# COIL-BOOST-10A.net
KiCad netlist of a schematic drawn in Altium Designer
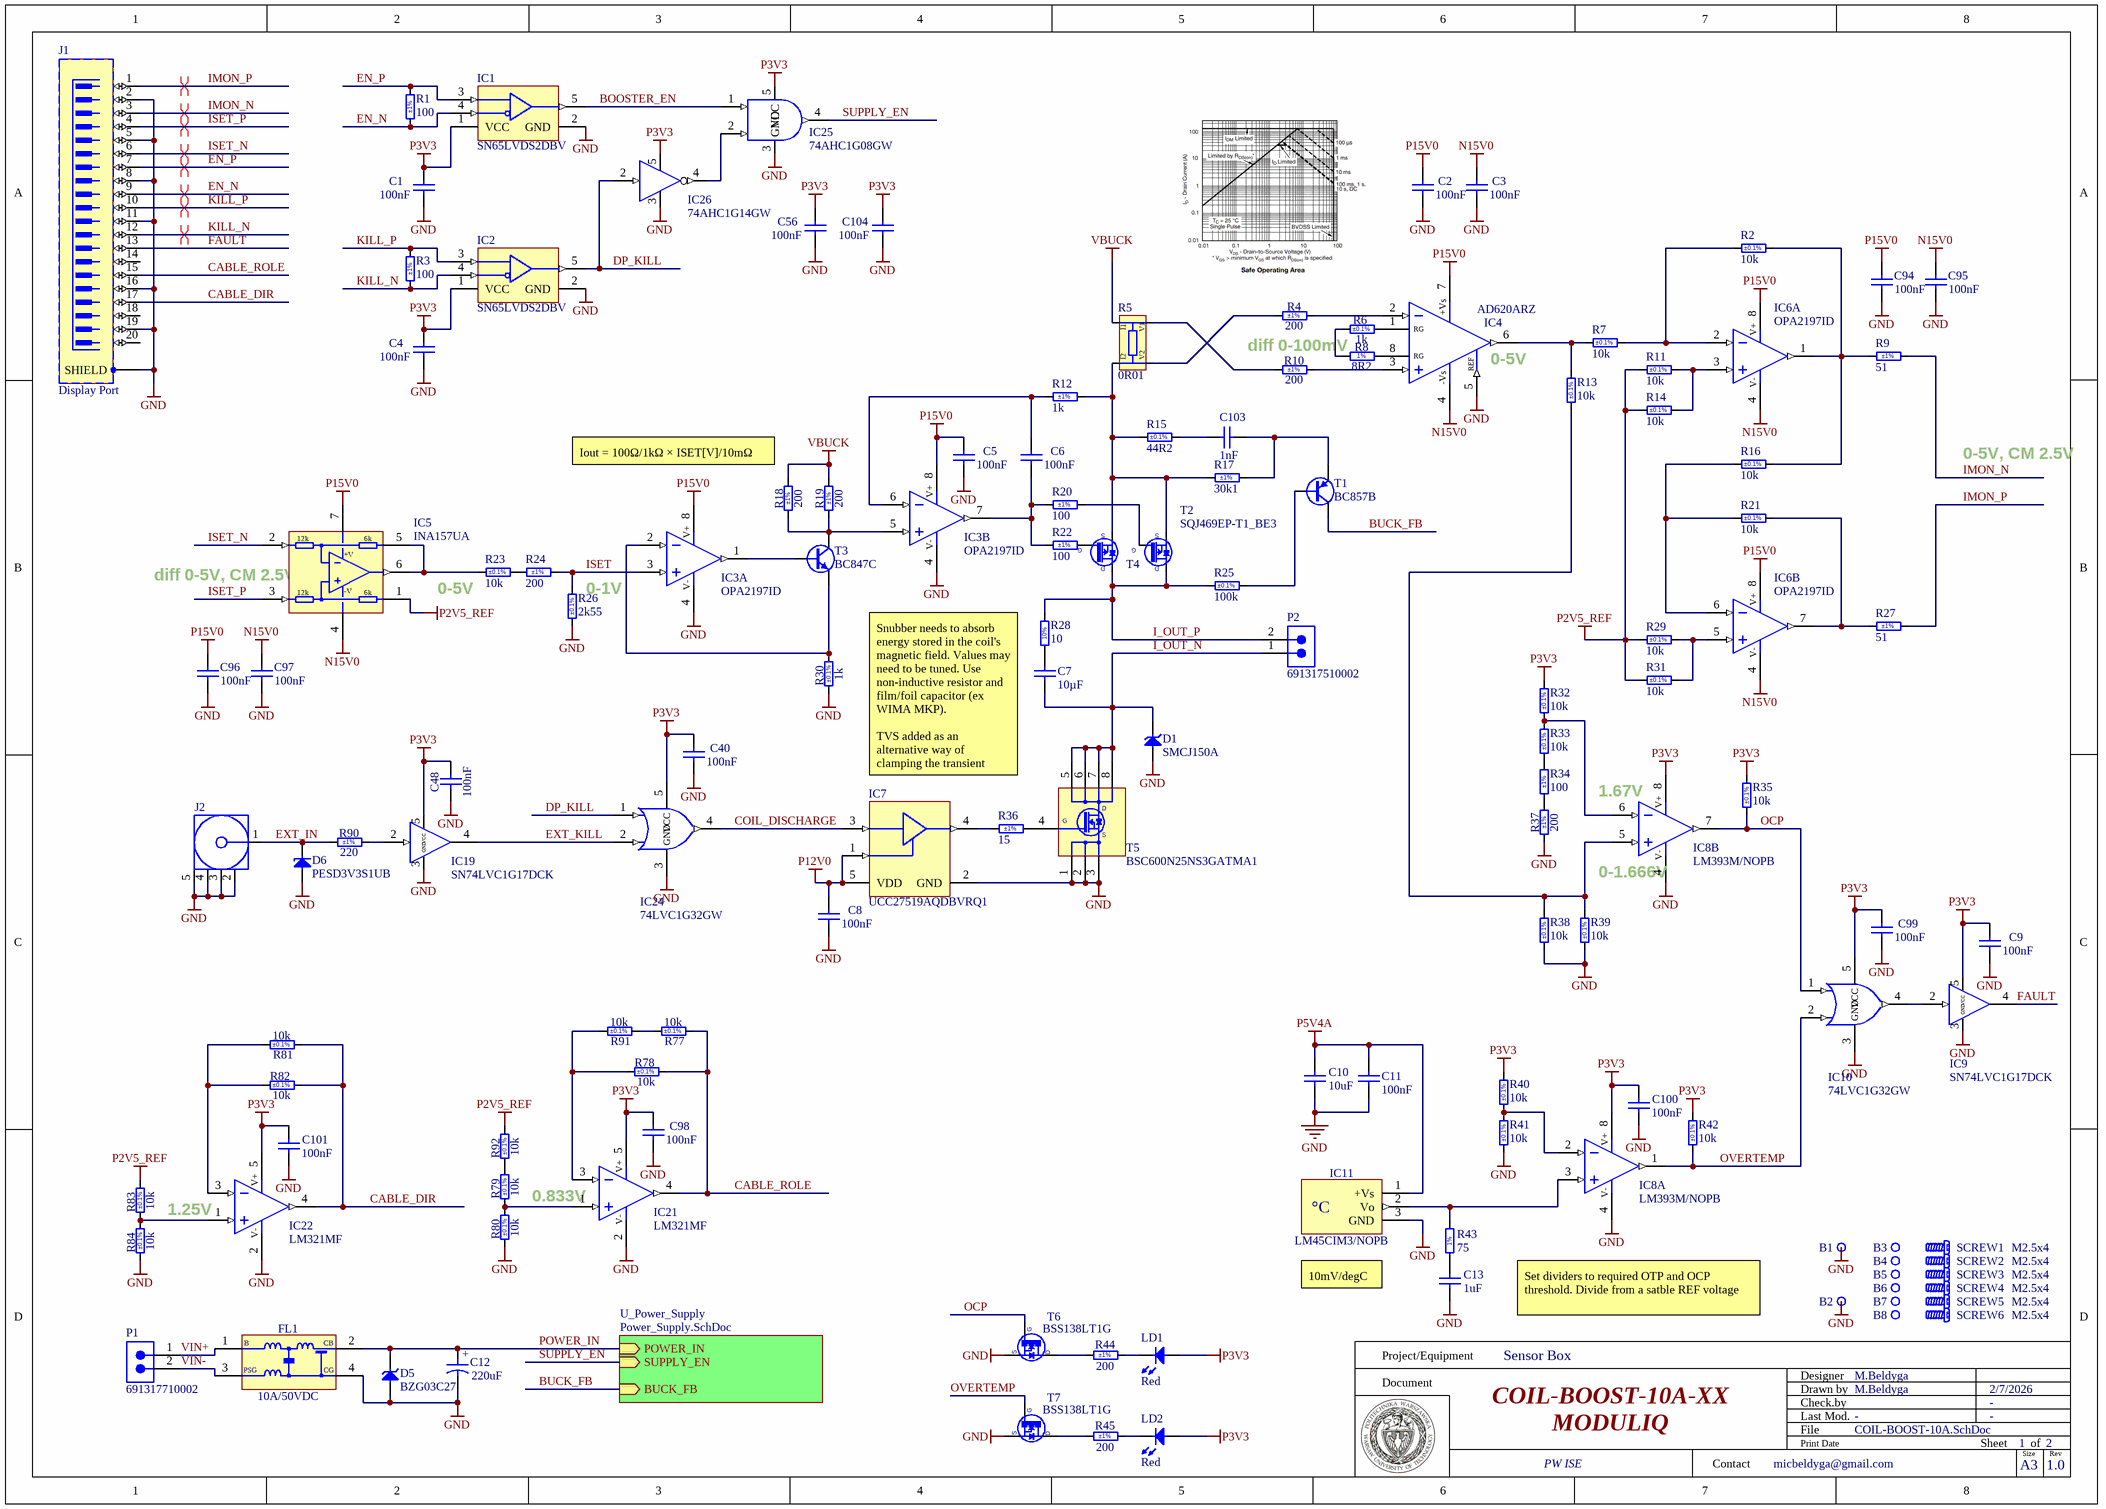
[diagram p0: COIL-BOOST-10A.SchDoc]

(export (version "E")
  (design (tool "Eeschema 10.0.6"))
  (components
    (comp (ref "B1")
      (value "Plated Hole")
      (footprint "MTG270_500")
      (description "Single Terminal Socket")
      (fields (field (name "PART NUMBER") "PLATED_HOLE2.7_PAD5.0") (field (name "AUTHOR") "CERN DEM JMW"))
      (libsource (lib "Eletro-mechanical") (part "Single Terminal Socket"))
    )
    (comp (ref "B2")
      (value "Plated Hole")
      (footprint "MTG270_500")
      (description "Single Terminal Socket")
      (fields (field (name "PART NUMBER") "PLATED_HOLE2.7_PAD5.0") (field (name "AUTHOR") "CERN DEM JMW"))
      (libsource (lib "Eletro-mechanical") (part "Single Terminal Socket"))
    )
    (comp (ref "B3")
      (value "Plated Hole")
      (footprint "MTG270_500")
      (description "Single Terminal Socket")
      (fields (field (name "PART NUMBER") "PLATED_HOLE2.7_PAD5.0") (field (name "AUTHOR") "CERN DEM JMW"))
      (libsource (lib "Eletro-mechanical") (part "Single Terminal Socket"))
    )
    (comp (ref "B4")
      (value "Plated Hole")
      (footprint "MTG270_500")
      (description "Single Terminal Socket")
      (fields (field (name "PART NUMBER") "PLATED_HOLE2.7_PAD5.0") (field (name "AUTHOR") "CERN DEM JMW"))
      (libsource (lib "Eletro-mechanical") (part "Single Terminal Socket"))
    )
    (comp (ref "B5")
      (value "Plated Hole")
      (footprint "MTG270_500")
      (description "Single Terminal Socket")
      (fields (field (name "PART NUMBER") "PLATED_HOLE2.7_PAD5.0") (field (name "AUTHOR") "CERN DEM JMW"))
      (libsource (lib "Eletro-mechanical") (part "Single Terminal Socket"))
    )
    (comp (ref "B6")
      (value "Plated Hole")
      (footprint "MTG270_500")
      (description "Single Terminal Socket")
      (fields (field (name "PART NUMBER") "PLATED_HOLE2.7_PAD5.0") (field (name "AUTHOR") "CERN DEM JMW"))
      (libsource (lib "Eletro-mechanical") (part "Single Terminal Socket"))
    )
    (comp (ref "B7")
      (value "Plated Hole")
      (footprint "MTG270_500")
      (description "Single Terminal Socket")
      (fields (field (name "PART NUMBER") "PLATED_HOLE2.7_PAD5.0") (field (name "AUTHOR") "CERN DEM JMW"))
      (libsource (lib "Eletro-mechanical") (part "Single Terminal Socket"))
    )
    (comp (ref "B8")
      (value "Plated Hole")
      (footprint "MTG270_500")
      (description "Single Terminal Socket")
      (fields (field (name "PART NUMBER") "PLATED_HOLE2.7_PAD5.0") (field (name "AUTHOR") "CERN DEM JMW"))
      (libsource (lib "Eletro-mechanical") (part "Single Terminal Socket"))
    )
    (comp (ref "C1")
      (value "100nF")
      (footprint "CAPC1005X55N")
      (description "Non-polarised capacitor")
      (fields
        (field (name "PART NUMBER") "CC0402_100NF_16V_10%_X5R")
        (field (name "VOLTAGE") "16V")
        (field (name "AUTHOR") "CERN DEM JLC")
      )
      (libsource (lib "Capacitors") (part "Capacitor - non polarized"))
    )
    (comp (ref "C2")
      (value "100nF")
      (footprint "CAPC1005X55N")
      (description "Non-polarised capacitor")
      (fields
        (field (name "PART NUMBER") "CC0402_100NF_16V_10%_X5R")
        (field (name "VOLTAGE") "16V")
        (field (name "AUTHOR") "CERN DEM JLC")
      )
      (libsource (lib "Capacitors") (part "Capacitor - non polarized"))
    )
    (comp (ref "C3")
      (value "100nF")
      (footprint "CAPC1005X55N")
      (description "Non-polarised capacitor")
      (fields
        (field (name "PART NUMBER") "CC0402_100NF_16V_10%_X5R")
        (field (name "VOLTAGE") "16V")
        (field (name "AUTHOR") "CERN DEM JLC")
      )
      (libsource (lib "Capacitors") (part "Capacitor - non polarized"))
    )
    (comp (ref "C4")
      (value "100nF")
      (footprint "CAPC1005X55N")
      (description "Non-polarised capacitor")
      (fields
        (field (name "PART NUMBER") "CC0402_100NF_16V_10%_X5R")
        (field (name "VOLTAGE") "16V")
        (field (name "AUTHOR") "CERN DEM JLC")
      )
      (libsource (lib "Capacitors") (part "Capacitor - non polarized"))
    )
    (comp (ref "C5")
      (value "100nF")
      (footprint "CAPC1005X55N")
      (description "Non-polarised capacitor")
      (fields
        (field (name "PART NUMBER") "CC0402_100NF_16V_10%_X5R")
        (field (name "VOLTAGE") "16V")
        (field (name "AUTHOR") "CERN DEM JLC")
      )
      (libsource (lib "Capacitors") (part "Capacitor - non polarized"))
    )
    (comp (ref "C6")
      (value "100nF")
      (footprint "CAPC1005X55N")
      (description "Non-polarised capacitor")
      (fields
        (field (name "PART NUMBER") "CC0402_100NF_16V_10%_X5R")
        (field (name "VOLTAGE") "16V")
        (field (name "AUTHOR") "CERN DEM JLC")
      )
      (libsource (lib "Capacitors") (part "Capacitor - non polarized"))
    )
    (comp (ref "C7")
      (value "10µF")
      (footprint "Kemet R71 32x28x14")
      (description "Film Capacitor, Polypropylene, 450V, 10% +Tol, 10% -Tol, 10uF, Through Hole Mount")
      (fields
        (field (name "MANUFACTURER") "KEMET")
        (field (name "MANUFACTURER PART NUMBER") "R71XR510050H0K")
      )
      (libsource (lib "mb") (part "R71XR510050H0K"))
    )
    (comp (ref "C8")
      (value "100nF")
      (footprint "CAPC1005X55N")
      (description "Non-polarised capacitor")
      (fields
        (field (name "PART NUMBER") "CC0402_100NF_16V_10%_X5R")
        (field (name "VOLTAGE") "16V")
        (field (name "AUTHOR") "CERN DEM JLC")
      )
      (libsource (lib "Capacitors") (part "Capacitor - non polarized"))
    )
    (comp (ref "C9")
      (value "100nF")
      (footprint "CAPC1005X55N")
      (description "Non-polarised capacitor")
      (fields
        (field (name "PART NUMBER") "CC0402_100NF_16V_10%_X5R")
        (field (name "VOLTAGE") "16V")
        (field (name "AUTHOR") "CERN DEM JLC")
      )
      (libsource (lib "Capacitors") (part "Capacitor - non polarized"))
    )
    (comp (ref "C10")
      (value "10uF")
      (footprint "CAPC1608X80N")
      (description "Non-polarised capacitor")
      (fields
        (field (name "PART NUMBER") "CC0603_10UF_10V_10%_X5R")
        (field (name "VOLTAGE") "10V")
        (field (name "AUTHOR") "CERN DEM JLC")
      )
      (libsource (lib "Capacitors") (part "Capacitor - non polarized"))
    )
    (comp (ref "C11")
      (value "100nF")
      (footprint "CAPC1005X55N")
      (description "Non-polarised capacitor")
      (fields
        (field (name "PART NUMBER") "CC0402_100NF_50V_10%_X7R")
        (field (name "VOLTAGE") "50V")
        (field (name "AUTHOR") "CERN DEM MR")
      )
      (libsource (lib "Capacitors") (part "Capacitor - non polarized"))
    )
    (comp (ref "C12")
      (value "220uF")
      (footprint "CAPAE830X620N")
      (description "Polarised capacitor")
      (fields
        (field (name "PART NUMBER") "CAE830-620_220UF_16V_20%")
        (field (name "VOLTAGE") "16V")
        (field (name "AUTHOR") "CERN DEM JLC")
      )
      (libsource (lib "Capacitors") (part "Capacitor - polarized"))
    )
    (comp (ref "C13")
      (value "1uF")
      (footprint "CAPC1005X55N")
      (description "Non-polarised capacitor")
      (fields
        (field (name "PART NUMBER") "CC0402_1UF_16V_10%_X5R")
        (field (name "VOLTAGE") "16V")
        (field (name "AUTHOR") "CERN DEM JLC")
      )
      (libsource (lib "Capacitors") (part "Capacitor - non polarized"))
    )
    (comp (ref "C40")
      (value "100nF")
      (footprint "CAPC1005X55N")
      (description "Non-polarised capacitor")
      (fields
        (field (name "PART NUMBER") "CC0402_100NF_16V_10%_X5R")
        (field (name "VOLTAGE") "16V")
        (field (name "AUTHOR") "CERN DEM JLC")
      )
      (libsource (lib "Capacitors") (part "Capacitor - non polarized"))
    )
    (comp (ref "C48")
      (value "100nF")
      (footprint "CAPC1005X55N")
      (description "Non-polarised capacitor")
      (fields
        (field (name "PART NUMBER") "CC0402_100NF_16V_10%_X7R")
        (field (name "VOLTAGE") "16V")
        (field (name "AUTHOR") "CERN DEM JLC")
      )
      (libsource (lib "Capacitors") (part "Capacitor - non polarized"))
    )
    (comp (ref "C56")
      (value "100nF")
      (footprint "CAPC1005X55N")
      (description "Non-polarised capacitor")
      (fields
        (field (name "PART NUMBER") "CC0402_100NF_16V_10%_X5R")
        (field (name "VOLTAGE") "16V")
        (field (name "AUTHOR") "CERN DEM JLC")
      )
      (libsource (lib "Capacitors") (part "Capacitor - non polarized"))
    )
    (comp (ref "C94")
      (value "100nF")
      (footprint "CAPC1005X55N")
      (description "Non-polarised capacitor")
      (fields
        (field (name "PART NUMBER") "CC0402_100NF_16V_10%_X5R")
        (field (name "VOLTAGE") "16V")
        (field (name "AUTHOR") "CERN DEM JLC")
      )
      (libsource (lib "Capacitors") (part "Capacitor - non polarized"))
    )
    (comp (ref "C95")
      (value "100nF")
      (footprint "CAPC1005X55N")
      (description "Non-polarised capacitor")
      (fields
        (field (name "PART NUMBER") "CC0402_100NF_16V_10%_X5R")
        (field (name "VOLTAGE") "16V")
        (field (name "AUTHOR") "CERN DEM JLC")
      )
      (libsource (lib "Capacitors") (part "Capacitor - non polarized"))
    )
    (comp (ref "C96")
      (value "100nF")
      (footprint "CAPC1005X55N")
      (description "Non-polarised capacitor")
      (fields
        (field (name "PART NUMBER") "CC0402_100NF_16V_10%_X5R")
        (field (name "VOLTAGE") "16V")
        (field (name "AUTHOR") "CERN DEM JLC")
      )
      (libsource (lib "Capacitors") (part "Capacitor - non polarized"))
    )
    (comp (ref "C97")
      (value "100nF")
      (footprint "CAPC1005X55N")
      (description "Non-polarised capacitor")
      (fields
        (field (name "PART NUMBER") "CC0402_100NF_16V_10%_X5R")
        (field (name "VOLTAGE") "16V")
        (field (name "AUTHOR") "CERN DEM JLC")
      )
      (libsource (lib "Capacitors") (part "Capacitor - non polarized"))
    )
    (comp (ref "C98")
      (value "100nF")
      (footprint "CAPC1005X55N")
      (description "Non-polarised capacitor")
      (fields
        (field (name "PART NUMBER") "CC0402_100NF_16V_10%_X5R")
        (field (name "VOLTAGE") "16V")
        (field (name "AUTHOR") "CERN DEM JLC")
      )
      (libsource (lib "Capacitors") (part "Capacitor - non polarized"))
    )
    (comp (ref "C99")
      (value "100nF")
      (footprint "CAPC1005X55N")
      (description "Non-polarised capacitor")
      (fields
        (field (name "PART NUMBER") "CC0402_100NF_16V_10%_X5R")
        (field (name "VOLTAGE") "16V")
        (field (name "AUTHOR") "CERN DEM JLC")
      )
      (libsource (lib "Capacitors") (part "Capacitor - non polarized"))
    )
    (comp (ref "C100")
      (value "100nF")
      (footprint "CAPC1005X55N")
      (description "Non-polarised capacitor")
      (fields
        (field (name "PART NUMBER") "CC0402_100NF_16V_10%_X5R")
        (field (name "VOLTAGE") "16V")
        (field (name "AUTHOR") "CERN DEM JLC")
      )
      (libsource (lib "Capacitors") (part "Capacitor - non polarized"))
    )
    (comp (ref "C101")
      (value "100nF")
      (footprint "CAPC1005X55N")
      (description "Non-polarised capacitor")
      (fields
        (field (name "PART NUMBER") "CC0402_100NF_16V_10%_X5R")
        (field (name "VOLTAGE") "16V")
        (field (name "AUTHOR") "CERN DEM JLC")
      )
      (libsource (lib "Capacitors") (part "Capacitor - non polarized"))
    )
    (comp (ref "C103")
      (value "1nF")
      (footprint "CAPC1005X55N")
      (description "Non-polarised capacitor")
      (fields
        (field (name "PART NUMBER") "CC0402_1NF_50V_5%_C0G")
        (field (name "VOLTAGE") "50V")
        (field (name "AUTHOR") "CERN DEM BC")
      )
      (libsource (lib "Capacitors") (part "Capacitor - non polarized"))
    )
    (comp (ref "C104")
      (value "100nF")
      (footprint "CAPC1005X55N")
      (description "Non-polarised capacitor")
      (fields
        (field (name "PART NUMBER") "CC0402_100NF_16V_10%_X5R")
        (field (name "VOLTAGE") "16V")
        (field (name "AUTHOR") "CERN DEM JLC")
      )
      (libsource (lib "Capacitors") (part "Capacitor - non polarized"))
    )
    (comp (ref "D1")
      (value "SMCJ150A")
      (footprint "DIOM7959X262N")
      (description "Transient Voltage Suppressor Diode (Uni-Directional)")
      (fields
        (field (name "VOLTAGE") "150V")
        (field (name "POWER") "1500W")
        (field (name "AUTHOR") "CERN DEM BC")
      )
      (libsource (lib "ICs And Semiconductors") (part "Diode TVS Uni-Directional"))
    )
    (comp (ref "D5")
      (value "BZG03C27")
      (footprint "DIOM5326X230N")
      (description "Zener Diode")
      (fields
        (field (name "VOLTAGE") "27V")
        (field (name "POWER") "1.25W")
        (field (name "AUTHOR") "CERN DEM JLC")
      )
      (libsource (lib "ICs And Semiconductors") (part "Diode Zener"))
    )
    (comp (ref "D6")
      (value "PESD3V3S1UB")
      (footprint "SODFL1608X65N")
      (description "ESD protection diode")
      (fields
        (field (name "VOLTAGE") "3V3")
        (field (name "POWER") "330W")
        (field (name "AUTHOR") "CERN DEM JLC")
      )
      (libsource (lib "ICs And Semiconductors") (part "Diode ESD"))
    )
    (comp (ref "FL1")
      (value "10A/50VDC")
      (footprint "FIL_MURATA_BNX02")
      (description "Block Type EMIFIL (LC Combined)")
      (fields
        (field (name "PART NUMBER") "FIL_MURATA_BNX022-01L")
        (field (name "MANUFACTURER1 PART NUMBER") "BNX022-01L")
        (field (name "AUTHOR") "CERN DEM JLC")
      )
      (libsource (lib "Inductors & Transformers") (part "FIL_MURATA_BNX02"))
    )
    (comp (ref "IC1")
      (value "SN65LVDS2DBV")
      (footprint "SOT95P280X145-5N")
      (description "High-Speed Differential Line Receiver")
      (fields
        (field (name "PART NUMBER") "SN65LVDS2DBVR")
        (field (name "MANUFACTURER") "TEXAS INSTRUMENTS")
        (field (name "AUTHOR") "CERN DEM JLC")
      )
      (libsource (lib "ICs And Semiconductors") (part "SN65LVDS2DBV"))
    )
    (comp (ref "IC2")
      (value "SN65LVDS2DBV")
      (footprint "SOT95P280X145-5N")
      (description "High-Speed Differential Line Receiver")
      (fields
        (field (name "PART NUMBER") "SN65LVDS2DBVR")
        (field (name "MANUFACTURER") "TEXAS INSTRUMENTS")
        (field (name "AUTHOR") "CERN DEM JLC")
      )
      (libsource (lib "ICs And Semiconductors") (part "SN65LVDS2DBV"))
    )
    (comp (ref "IC3")
      (value "OPA2197ID")
      (footprint "SOIC127P600X175-8N")
      (description "Dual Operational Amplifier")
      (fields (field (name "MANUFACTURER") "TEXAS INSTRUMENTS") (field (name "AUTHOR") "CERN DEM MR"))
      (libsource (lib "ICs And Semiconductors") (part "Operational Amplifier x2 Type1"))
    )
    (comp (ref "IC4")
      (value "AD620ARZ")
      (footprint "SOIC127P600X175-8N")
      (description "Low Cost Low Power Instrumentation Amplifier")
      (fields
        (field (name "MANUFACTURER1 PART NUMBER") "AD620ARZ-REEL7")
        (field (name "AUTHOR") "CERN DEM JLC")
      )
      (libsource (lib "ICs And Semiconductors") (part "AD620"))
    )
    (comp (ref "IC5")
      (value "INA157UA")
      (footprint "SOIC127P600X175-8N")
      (description "IC OPAMP DIFF 1 CIRCUIT 8SOIC Differential Amplifier 1 Circuit 8-SOIC")
      (fields (field (name "MANUFACTURER") "Texas Instruments"))
      (libsource (lib "mb") (part "INA157UA"))
    )
    (comp (ref "IC6")
      (value "OPA2197ID")
      (footprint "SOIC127P600X175-8N")
      (description "Dual Operational Amplifier")
      (fields (field (name "MANUFACTURER") "TEXAS INSTRUMENTS") (field (name "AUTHOR") "CERN DEM MR"))
      (libsource (lib "ICs And Semiconductors") (part "Operational Amplifier x2 Type1"))
    )
    (comp (ref "IC7")
      (value "UCC27519AQDBVRQ1")
      (footprint "SOT95P280X145-5N")
      (description "Single-Channel High-Speed Low-Side Gate Driver With Negative Input  Voltage Capability")
      (fields
        (field (name "MANUFACTURER") "TEXAS INSTRUMENTS")
        (field (name "MANUFACTURER PART NUMBER") "UCC27519AQDBV")
        (field (name "AUTHOR") "CERN DEM JLC")
      )
      (libsource (lib "ICs And Semiconductors") (part "UCC2751xA-Q1"))
    )
    (comp (ref "IC8")
      (value "LM393M/NOPB")
      (footprint "SOIC127P600X175-8N")
      (description "Dual Operational Amplifier")
      (fields
        (field (name "MANUFACTURER") "NATIONAL SEMICONDUCTOR")
        (field (name "MANUFACTURER PART NUMBER") "LM393M")
        (field (name "AUTHOR") "CERN DEM JLC")
      )
      (libsource (lib "ICs And Semiconductors") (part "Operational Amplifier x2 Type1"))
    )
    (comp (ref "IC9")
      (value "SN74LVC1G17DCK")
      (footprint "SOT65P210X110-5N")
      (description "Single Schmitt-Trigger Buffer")
      (fields (field (name "MANUFACTURER") "TEXAS INSTRUMENTS") (field (name "AUTHOR") "CERN DEM HF"))
      (libsource (lib "mb") (part "SN74LVC1G17DCK"))
    )
    (comp (ref "IC10")
      (value "74LVC1G32GW")
      (footprint "SOT65P212X110-5N")
      (description "Single 2-Input Positive-OR Gate")
      (fields (field (name "MANUFACTURER") "NXP SEMICONDUCTORS") (field (name "AUTHOR") "CERN DEM JLC"))
      (libsource (lib "ICs And Semiconductors") (part "741G32"))
    )
    (comp (ref "IC11")
      (value "LM45CIM3/NOPB")
      (footprint "SOT95P251X112-3N")
      (description "-20° to +100°C ±3°C Precision Centigrade Temperature Sensors")
      (fields (field (name "MANUFACTURER") "TEXAS INSTRUMENTS") (field (name "AUTHOR") "CERN DEM JLC"))
      (libsource (lib "ICs And Semiconductors") (part "LM45"))
    )
    (comp (ref "IC19")
      (value "SN74LVC1G17DCK")
      (footprint "SOT65P210X110-5N")
      (description "Single Schmitt-Trigger Buffer")
      (fields (field (name "MANUFACTURER") "TEXAS INSTRUMENTS") (field (name "AUTHOR") "CERN DEM HF"))
      (libsource (lib "mb") (part "SN74LVC1G17DCK"))
    )
    (comp (ref "IC21")
      (value "LM321MF")
      (footprint "SOT95P280X145-5N")
      (description "Low Power Single Operational Amplifier")
      (fields
        (field (name "PART NUMBER") "LM321MF/NOPB")
        (field (name "MANUFACTURER") "TEXAS INSTRUMENTS")
        (field (name "AUTHOR") "CERN DEM BC")
      )
      (libsource (lib "ICs And Semiconductors") (part "LM321"))
    )
    (comp (ref "IC22")
      (value "LM321MF")
      (footprint "SOT95P280X145-5N")
      (description "Low Power Single Operational Amplifier")
      (fields
        (field (name "PART NUMBER") "LM321MF/NOPB")
        (field (name "MANUFACTURER") "TEXAS INSTRUMENTS")
        (field (name "AUTHOR") "CERN DEM BC")
      )
      (libsource (lib "ICs And Semiconductors") (part "LM321"))
    )
    (comp (ref "IC24")
      (value "74LVC1G32GW")
      (footprint "SOT65P212X110-5N")
      (description "Single 2-Input Positive-OR Gate")
      (fields (field (name "MANUFACTURER") "NXP SEMICONDUCTORS") (field (name "AUTHOR") "CERN DEM JLC"))
      (libsource (lib "ICs And Semiconductors") (part "741G32"))
    )
    (comp (ref "IC25")
      (value "74AHC1G08GW")
      (footprint "SOT65P212X110-5N")
      (description "Single 2-Input AND Gate")
      (fields (field (name "MANUFACTURER") "NXP SEMICONDUCTORS") (field (name "AUTHOR") "CERN DEM JLC"))
      (libsource (lib "ICs And Semiconductors") (part "741G08"))
    )
    (comp (ref "IC26")
      (value "74AHC1G14GW")
      (footprint "SOT65P212X110-5N")
      (description "Single Schmitt-Trigger Inverter")
      (fields (field (name "MANUFACTURER") "NXP SEMICONDUCTORS") (field (name "AUTHOR") "CERN DEM JMW"))
      (libsource (lib "ICs And Semiconductors") (part "741G14"))
    )
    (comp (ref "J1")
      (value "Display Port")
      (footprint "MOLEX_47272-0001")
      (description "Connector Mini DisplayPort 20 Male + 1 Shield")
      (fields
        (field (name "PART NUMBER") "MOLEX_47272-0001")
        (field (name "MANUFACTURER") "MOLEX")
        (field (name "AUTHOR") "CERN DEM JLC")
      )
      (libsource (lib "Connectors") (part "Connector Mini DisplayPort 20 Male + 1 Shield"))
    )
    (comp (ref "J2")
      (value "60611002111502")
      (footprint "60611002111502")
      (description "WR-MCX PCB Jack, THT, Right Angle, Solder Leg 1.73mm")
      (fields (field (name "MANUFACTURER") "Wurth Elektronik"))
      (libsource (lib "Altium_WR-MCX (rev22a)") (part "60611002111502"))
    )
    (comp (ref "LD1")
      (value "Red")
      (footprint "LED_AVAGO_HSMC-C120")
      (description "LED Red 1C 2A")
      (fields
        (field (name "PART NUMBER") "LED_AVAGO_HSMC-C120")
        (field (name "MANUFACTURER") "AVAGO TECHNOLOGIES")
        (field (name "AUTHOR") "CERN DEM JMW")
      )
      (libsource (lib "ICs And Semiconductors") (part "LED Red 1C 2A"))
    )
    (comp (ref "LD2")
      (value "Red")
      (footprint "LED_AVAGO_HSMC-C120")
      (description "LED Red 1C 2A")
      (fields
        (field (name "PART NUMBER") "LED_AVAGO_HSMC-C120")
        (field (name "MANUFACTURER") "AVAGO TECHNOLOGIES")
        (field (name "AUTHOR") "CERN DEM JMW")
      )
      (libsource (lib "ICs And Semiconductors") (part "LED Red 1C 2A"))
    )
    (comp (ref "P1")
      (value "691317710002")
      (footprint "691317710002")
      (description "WR-TBL Series 3177 Close Horizontal PCB Header with Flanges, THT, pitch 5mm, 2p")
      (fields (field (name "MANUFACTURER") "Wurth Elektronik"))
      (libsource (lib "WE - Electromechanical Components") (part "TBL - 1R - 02P - Male"))
    )
    (comp (ref "P2")
      (value "691317510002")
      (footprint "691317510002")
      (description "WR-TBL Series 3175 Close Horizontal PCB Header with Flanges, THT, pitch 5.08mm, 2p")
      (fields (field (name "MANUFACTURER") "Wurth Elektronik"))
      (libsource (lib "WE - Electromechanical Components") (part "TBL - 1R - 02P - Male"))
    )
    (comp (ref "R1")
      (value "100")
      (footprint "RESC1005X40N")
      (description "Resistor - 1%")
      (fields
        (field (name "TOLERANCE") "±1%")
        (field (name "PART NUMBER") "R0402_100R_1%_0.0625W_100PPM")
        (field (name "POWER") "0.0625W")
        (field (name "AUTHOR") "CERN DEM JLC")
      )
      (libsource (lib "Resistors") (part "Resistor - 1%"))
    )
    (comp (ref "R2")
      (value "10k")
      (footprint "RESC1005X35N")
      (description "Resistor - 0.1%")
      (fields
        (field (name "TOLERANCE") "±0.1%")
        (field (name "PART NUMBER") "R0402_10K_0.1%_0.063W_25PPM")
        (field (name "POWER") "0.063W")
        (field (name "AUTHOR") "CERN DEM JMW")
      )
      (libsource (lib "Resistors") (part "Resistor - 0.1%"))
    )
    (comp (ref "R3")
      (value "100")
      (footprint "RESC1005X40N")
      (description "Resistor - 1%")
      (fields
        (field (name "TOLERANCE") "±1%")
        (field (name "PART NUMBER") "R0402_100R_1%_0.0625W_100PPM")
        (field (name "POWER") "0.0625W")
        (field (name "AUTHOR") "CERN DEM JLC")
      )
      (libsource (lib "Resistors") (part "Resistor - 1%"))
    )
    (comp (ref "R4")
      (value "200")
      (footprint "RESC1608X55N")
      (description "Resistor - 1%")
      (fields
        (field (name "TOLERANCE") "±1%")
        (field (name "PART NUMBER") "R0603_200R_1%_0.1W_100PPM")
        (field (name "POWER") "0.1W")
        (field (name "AUTHOR") "CERN DEM JLC")
      )
      (libsource (lib "Resistors") (part "Resistor - 1%"))
    )
    (comp (ref "R5")
      (value "0R01")
      (footprint "RES_OHMITE_LVK25")
      (description "Power and Current Sensing Resistor")
      (fields
        (field (name "PART NUMBER") "R_0R01_1%_2W_100PPM_OHMITE_LVK25")
        (field (name "POWER") "2W")
        (field (name "AUTHOR") "CERN DEM BC")
      )
      (libsource (lib "Resistors") (part "Current + Voltage Sense Resistor"))
    )
    (comp (ref "R6")
      (value "1k")
      (footprint "RESC1608X55N")
      (description "Resistor - 0.1%")
      (fields
        (field (name "TOLERANCE") "±0.1%")
        (field (name "PART NUMBER") "R0603_1K_0.1%_0.063W_10PPM")
        (field (name "POWER") "0.063W")
        (field (name "AUTHOR") "CERN DEM BC")
      )
      (libsource (lib "Resistors") (part "Resistor - 0.1%"))
    )
    (comp (ref "R7")
      (value "10k")
      (footprint "RESC1005X35N")
      (description "Resistor - 0.1%")
      (fields
        (field (name "TOLERANCE") "±0.1%")
        (field (name "PART NUMBER") "R0402_10K_0.1%_0.063W_25PPM")
        (field (name "POWER") "0.063W")
        (field (name "AUTHOR") "CERN DEM JMW")
      )
      (libsource (lib "Resistors") (part "Resistor - 0.1%"))
    )
    (comp (ref "R8")
      (value "8R2")
      (footprint "RESC1608X55N")
      (description "Resistor - 1%")
      (fields
        (field (name "PART NUMBER") "R0603_8R2_1%_0.1W_200PPM")
        (field (name "POWER") "0.1W")
        (field (name "AUTHOR") "CERN DEM JLC")
      )
      (libsource (lib "Resistors") (part "Resistor - 1%"))
    )
    (comp (ref "R9")
      (value "51")
      (footprint "RESC1608X55N")
      (description "Resistor - 1%")
      (fields
        (field (name "TOLERANCE") "±1%")
        (field (name "PART NUMBER") "R0603_51R_1%_0.1W_100PPM")
        (field (name "POWER") "0.1W")
        (field (name "AUTHOR") "CERN DEM JLC")
      )
      (libsource (lib "Resistors") (part "Resistor - 1%"))
    )
    (comp (ref "R10")
      (value "200")
      (footprint "RESC1608X55N")
      (description "Resistor - 1%")
      (fields
        (field (name "TOLERANCE") "±1%")
        (field (name "PART NUMBER") "R0603_200R_1%_0.1W_100PPM")
        (field (name "POWER") "0.1W")
        (field (name "AUTHOR") "CERN DEM JLC")
      )
      (libsource (lib "Resistors") (part "Resistor - 1%"))
    )
    (comp (ref "R11")
      (value "10k")
      (footprint "RESC1005X35N")
      (description "Resistor - 0.1%")
      (fields
        (field (name "TOLERANCE") "±0.1%")
        (field (name "PART NUMBER") "R0402_10K_0.1%_0.063W_25PPM")
        (field (name "POWER") "0.063W")
        (field (name "AUTHOR") "CERN DEM JMW")
      )
      (libsource (lib "Resistors") (part "Resistor - 0.1%"))
    )
    (comp (ref "R12")
      (value "1k")
      (footprint "RESC1005X40N")
      (description "Resistor - 1%")
      (fields
        (field (name "TOLERANCE") "±1%")
        (field (name "PART NUMBER") "R0402_1K_1%_0.0625W_100PPM")
        (field (name "POWER") "0.0625W")
        (field (name "AUTHOR") "CERN DEM JLC")
      )
      (libsource (lib "Resistors") (part "Resistor - 1%"))
    )
    (comp (ref "R13")
      (value "10k")
      (footprint "RESC1005X35N")
      (description "Resistor - 0.1%")
      (fields
        (field (name "TOLERANCE") "±0.1%")
        (field (name "PART NUMBER") "R0402_10K_0.1%_0.063W_25PPM")
        (field (name "POWER") "0.063W")
        (field (name "AUTHOR") "CERN DEM JMW")
      )
      (libsource (lib "Resistors") (part "Resistor - 0.1%"))
    )
    (comp (ref "R14")
      (value "10k")
      (footprint "RESC1005X35N")
      (description "Resistor - 0.1%")
      (fields
        (field (name "TOLERANCE") "±0.1%")
        (field (name "PART NUMBER") "R0402_10K_0.1%_0.063W_25PPM")
        (field (name "POWER") "0.063W")
        (field (name "AUTHOR") "CERN DEM JMW")
      )
      (libsource (lib "Resistors") (part "Resistor - 0.1%"))
    )
    (comp (ref "R15")
      (value "44R2")
      (footprint "RESC1608X55N")
      (description "Resistor - 0.1%")
      (fields
        (field (name "TOLERANCE") "±0.1%")
        (field (name "PART NUMBER") "R0603_44R2_0.1%_0.063W_10PPM")
        (field (name "POWER") "0.063W")
        (field (name "AUTHOR") "CERN DEM JLC")
      )
      (libsource (lib "Resistors") (part "Resistor - 0.1%"))
    )
    (comp (ref "R16")
      (value "10k")
      (footprint "RESC1005X35N")
      (description "Resistor - 0.1%")
      (fields
        (field (name "TOLERANCE") "±0.1%")
        (field (name "PART NUMBER") "R0402_10K_0.1%_0.063W_25PPM")
        (field (name "POWER") "0.063W")
        (field (name "AUTHOR") "CERN DEM JMW")
      )
      (libsource (lib "Resistors") (part "Resistor - 0.1%"))
    )
    (comp (ref "R17")
      (value "30k1")
      (footprint "RESC1005X40N")
      (description "Resistor - 1%")
      (fields
        (field (name "TOLERANCE") "±1%")
        (field (name "PART NUMBER") "R0402_30K1_1%_0.0625W_100PPM")
        (field (name "POWER") "0.0625W")
        (field (name "AUTHOR") "CERN DEM BC")
      )
      (libsource (lib "Resistors") (part "Resistor - 1%"))
    )
    (comp (ref "R18")
      (value "200")
      (footprint "RESC1608X55N")
      (description "Resistor - 1%")
      (fields
        (field (name "TOLERANCE") "±1%")
        (field (name "PART NUMBER") "R0603_200R_1%_0.1W_100PPM")
        (field (name "POWER") "0.1W")
        (field (name "AUTHOR") "CERN DEM JLC")
      )
      (libsource (lib "Resistors") (part "Resistor - 1%"))
    )
    (comp (ref "R19")
      (value "200")
      (footprint "RESC1608X55N")
      (description "Resistor - 1%")
      (fields
        (field (name "TOLERANCE") "±1%")
        (field (name "PART NUMBER") "R0603_200R_1%_0.1W_100PPM")
        (field (name "POWER") "0.1W")
        (field (name "AUTHOR") "CERN DEM JLC")
      )
      (libsource (lib "Resistors") (part "Resistor - 1%"))
    )
    (comp (ref "R20")
      (value "100")
      (footprint "RESC1005X40N")
      (description "Resistor - 1%")
      (fields
        (field (name "TOLERANCE") "±1%")
        (field (name "PART NUMBER") "R0402_100R_1%_0.0625W_100PPM")
        (field (name "POWER") "0.0625W")
        (field (name "AUTHOR") "CERN DEM JLC")
      )
      (libsource (lib "Resistors") (part "Resistor - 1%"))
    )
    (comp (ref "R21")
      (value "10k")
      (footprint "RESC1005X35N")
      (description "Resistor - 0.1%")
      (fields
        (field (name "TOLERANCE") "±0.1%")
        (field (name "PART NUMBER") "R0402_10K_0.1%_0.063W_25PPM")
        (field (name "POWER") "0.063W")
        (field (name "AUTHOR") "CERN DEM JMW")
      )
      (libsource (lib "Resistors") (part "Resistor - 0.1%"))
    )
    (comp (ref "R22")
      (value "100")
      (footprint "RESC1005X40N")
      (description "Resistor - 1%")
      (fields
        (field (name "TOLERANCE") "±1%")
        (field (name "PART NUMBER") "R0402_100R_1%_0.0625W_100PPM")
        (field (name "POWER") "0.0625W")
        (field (name "AUTHOR") "CERN DEM JLC")
      )
      (libsource (lib "Resistors") (part "Resistor - 1%"))
    )
    (comp (ref "R23")
      (value "10k")
      (footprint "RESC1005X35N")
      (description "Resistor - 0.1%")
      (fields
        (field (name "TOLERANCE") "±0.1%")
        (field (name "PART NUMBER") "R0402_10K_0.1%_0.063W_25PPM")
        (field (name "POWER") "0.063W")
        (field (name "AUTHOR") "CERN DEM JMW")
      )
      (libsource (lib "Resistors") (part "Resistor - 0.1%"))
    )
    (comp (ref "R24")
      (value "200")
      (footprint "RESC1608X55N")
      (description "Resistor - 1%")
      (fields
        (field (name "TOLERANCE") "±1%")
        (field (name "PART NUMBER") "R0603_200R_1%_0.1W_100PPM")
        (field (name "POWER") "0.1W")
        (field (name "AUTHOR") "CERN DEM JLC")
      )
      (libsource (lib "Resistors") (part "Resistor - 1%"))
    )
    (comp (ref "R25")
      (value "100k")
      (footprint "RESC1005X35N")
      (description "Resistor - 0.1%")
      (fields
        (field (name "TOLERANCE") "±0.1%")
        (field (name "PART NUMBER") "R0402_100K_0.1%_0.063W_25PPM")
        (field (name "POWER") "0.063W")
        (field (name "AUTHOR") "CERN DEM JMW")
      )
      (libsource (lib "Resistors") (part "Resistor - 0.1%"))
    )
    (comp (ref "R26")
      (value "2k55")
      (footprint "RESC1608X55N")
      (description "Resistor - 0.1%")
      (fields
        (field (name "TOLERANCE") "±0.1%")
        (field (name "PART NUMBER") "R0603_2K55_0.1%_0.063W_10PPM")
        (field (name "POWER") "0.063W")
        (field (name "AUTHOR") "CERN DEM JLC")
      )
      (libsource (lib "Resistors") (part "Resistor - 0.1%"))
    )
    (comp (ref "R27")
      (value "51")
      (footprint "RESC1608X55N")
      (description "Resistor - 1%")
      (fields
        (field (name "TOLERANCE") "±1%")
        (field (name "PART NUMBER") "R0603_51R_1%_0.1W_100PPM")
        (field (name "POWER") "0.1W")
        (field (name "AUTHOR") "CERN DEM JLC")
      )
      (libsource (lib "Resistors") (part "Resistor - 1%"))
    )
    (comp (ref "R28")
      (value "10")
      (footprint "RES_OHMITE_OY_mb")
      (description "Resistor - 10%")
      (fields
        (field (name "PART NUMBER") "RCF_10R_10%_2W_-1300±300PPM_OHMITE_OY")
        (field (name "POWER") "2W")
        (field (name "AUTHOR") "CERN DEM MR")
      )
      (libsource (lib "Resistors") (part "Resistor - 10%"))
    )
    (comp (ref "R29")
      (value "10k")
      (footprint "RESC1005X35N")
      (description "Resistor - 0.1%")
      (fields
        (field (name "TOLERANCE") "±0.1%")
        (field (name "PART NUMBER") "R0402_10K_0.1%_0.063W_25PPM")
        (field (name "POWER") "0.063W")
        (field (name "AUTHOR") "CERN DEM JMW")
      )
      (libsource (lib "Resistors") (part "Resistor - 0.1%"))
    )
    (comp (ref "R30")
      (value "1k")
      (footprint "RESC1608X55N")
      (description "Resistor - 0.1%")
      (fields
        (field (name "TOLERANCE") "±0.1%")
        (field (name "PART NUMBER") "R0603_1K_0.1%_0.063W_10PPM")
        (field (name "POWER") "0.063W")
        (field (name "AUTHOR") "CERN DEM BC")
      )
      (libsource (lib "Resistors") (part "Resistor - 0.1%"))
    )
    (comp (ref "R31")
      (value "10k")
      (footprint "RESC1005X35N")
      (description "Resistor - 0.1%")
      (fields
        (field (name "TOLERANCE") "±0.1%")
        (field (name "PART NUMBER") "R0402_10K_0.1%_0.063W_25PPM")
        (field (name "POWER") "0.063W")
        (field (name "AUTHOR") "CERN DEM JMW")
      )
      (libsource (lib "Resistors") (part "Resistor - 0.1%"))
    )
    (comp (ref "R32")
      (value "10k")
      (footprint "RESC1005X35N")
      (description "Resistor - 0.1%")
      (fields
        (field (name "TOLERANCE") "±0.1%")
        (field (name "PART NUMBER") "R0402_10K_0.1%_0.063W_25PPM")
        (field (name "POWER") "0.063W")
        (field (name "AUTHOR") "CERN DEM JMW")
      )
      (libsource (lib "Resistors") (part "Resistor - 0.1%"))
    )
    (comp (ref "R33")
      (value "10k")
      (footprint "RESC1005X35N")
      (description "Resistor - 0.1%")
      (fields
        (field (name "TOLERANCE") "±0.1%")
        (field (name "PART NUMBER") "R0402_10K_0.1%_0.063W_25PPM")
        (field (name "POWER") "0.063W")
        (field (name "AUTHOR") "CERN DEM JMW")
      )
      (libsource (lib "Resistors") (part "Resistor - 0.1%"))
    )
    (comp (ref "R34")
      (value "100")
      (footprint "RESC1005X40N")
      (description "Resistor - 1%")
      (fields
        (field (name "TOLERANCE") "±1%")
        (field (name "PART NUMBER") "R0402_100R_1%_0.0625W_100PPM")
        (field (name "POWER") "0.0625W")
        (field (name "AUTHOR") "CERN DEM JLC")
      )
      (libsource (lib "Resistors") (part "Resistor - 1%"))
    )
    (comp (ref "R35")
      (value "10k")
      (footprint "RESC1005X35N")
      (description "Resistor - 0.1%")
      (fields
        (field (name "TOLERANCE") "±0.1%")
        (field (name "PART NUMBER") "R0402_10K_0.1%_0.063W_25PPM")
        (field (name "POWER") "0.063W")
        (field (name "AUTHOR") "CERN DEM JMW")
      )
      (libsource (lib "Resistors") (part "Resistor - 0.1%"))
    )
    (comp (ref "R36")
      (value "15")
      (footprint "RESC3216X65N")
      (description "Resistor - 1%")
      (fields
        (field (name "TOLERANCE") "±1%")
        (field (name "PART NUMBER") "R1206_15R_1%_0.25W_100PPM")
        (field (name "POWER") "0.25W")
        (field (name "AUTHOR") "CERN DEM JLC")
      )
      (libsource (lib "Resistors") (part "Resistor - 1%"))
    )
    (comp (ref "R37")
      (value "200")
      (footprint "RESC1608X55N")
      (description "Resistor - 1%")
      (fields
        (field (name "TOLERANCE") "±1%")
        (field (name "PART NUMBER") "R0603_200R_1%_0.1W_100PPM")
        (field (name "POWER") "0.1W")
        (field (name "AUTHOR") "CERN DEM JLC")
      )
      (libsource (lib "Resistors") (part "Resistor - 1%"))
    )
    (comp (ref "R38")
      (value "10k")
      (footprint "RESC1005X35N")
      (description "Resistor - 0.1%")
      (fields
        (field (name "TOLERANCE") "±0.1%")
        (field (name "PART NUMBER") "R0402_10K_0.1%_0.063W_25PPM")
        (field (name "POWER") "0.063W")
        (field (name "AUTHOR") "CERN DEM JMW")
      )
      (libsource (lib "Resistors") (part "Resistor - 0.1%"))
    )
    (comp (ref "R39")
      (value "10k")
      (footprint "RESC1005X35N")
      (description "Resistor - 0.1%")
      (fields
        (field (name "TOLERANCE") "±0.1%")
        (field (name "PART NUMBER") "R0402_10K_0.1%_0.063W_25PPM")
        (field (name "POWER") "0.063W")
        (field (name "AUTHOR") "CERN DEM JMW")
      )
      (libsource (lib "Resistors") (part "Resistor - 0.1%"))
    )
    (comp (ref "R40")
      (value "10k")
      (footprint "RESC1005X35N")
      (description "Resistor - 0.1%")
      (fields
        (field (name "TOLERANCE") "±0.1%")
        (field (name "PART NUMBER") "R0402_10K_0.1%_0.063W_25PPM")
        (field (name "POWER") "0.063W")
        (field (name "AUTHOR") "CERN DEM JMW")
      )
      (libsource (lib "Resistors") (part "Resistor - 0.1%"))
    )
    (comp (ref "R41")
      (value "10k")
      (footprint "RESC1005X35N")
      (description "Resistor - 0.1%")
      (fields
        (field (name "TOLERANCE") "±0.1%")
        (field (name "PART NUMBER") "R0402_10K_0.1%_0.063W_25PPM")
        (field (name "POWER") "0.063W")
        (field (name "AUTHOR") "CERN DEM JMW")
      )
      (libsource (lib "Resistors") (part "Resistor - 0.1%"))
    )
    (comp (ref "R42")
      (value "10k")
      (footprint "RESC1005X35N")
      (description "Resistor - 0.1%")
      (fields
        (field (name "TOLERANCE") "±0.1%")
        (field (name "PART NUMBER") "R0402_10K_0.1%_0.063W_25PPM")
        (field (name "POWER") "0.063W")
        (field (name "AUTHOR") "CERN DEM JMW")
      )
      (libsource (lib "Resistors") (part "Resistor - 0.1%"))
    )
    (comp (ref "R43")
      (value "75")
      (footprint "RESC1005X40N")
      (description "Resistor - 1%")
      (fields
        (field (name "PART NUMBER") "R0402_75R_1%_0.0625W_100PPM")
        (field (name "POWER") "0.0625W")
        (field (name "AUTHOR") "CERN DEM JLC")
      )
      (libsource (lib "") (part "Resistor - 1%_1"))
    )
    (comp (ref "R44")
      (value "200")
      (footprint "RESC1608X55N")
      (description "Resistor - 1%")
      (fields
        (field (name "TOLERANCE") "±1%")
        (field (name "PART NUMBER") "R0603_200R_1%_0.1W_100PPM")
        (field (name "POWER") "0.1W")
        (field (name "AUTHOR") "CERN DEM JLC")
      )
      (libsource (lib "Resistors") (part "Resistor - 1%"))
    )
    (comp (ref "R45")
      (value "200")
      (footprint "RESC1608X55N")
      (description "Resistor - 1%")
      (fields
        (field (name "TOLERANCE") "±1%")
        (field (name "PART NUMBER") "R0603_200R_1%_0.1W_100PPM")
        (field (name "POWER") "0.1W")
        (field (name "AUTHOR") "CERN DEM JLC")
      )
      (libsource (lib "Resistors") (part "Resistor - 1%"))
    )
    (comp (ref "R77")
      (value "10k")
      (footprint "RESC1005X35N")
      (description "Resistor - 0.1%")
      (fields
        (field (name "TOLERANCE") "±0.1%")
        (field (name "PART NUMBER") "R0402_10K_0.1%_0.063W_25PPM")
        (field (name "POWER") "0.063W")
        (field (name "AUTHOR") "CERN DEM JMW")
      )
      (libsource (lib "Resistors") (part "Resistor - 0.1%"))
    )
    (comp (ref "R78")
      (value "10k")
      (footprint "RESC1005X35N")
      (description "Resistor - 0.1%")
      (fields
        (field (name "TOLERANCE") "±0.1%")
        (field (name "PART NUMBER") "R0402_10K_0.1%_0.063W_25PPM")
        (field (name "POWER") "0.063W")
        (field (name "AUTHOR") "CERN DEM JMW")
      )
      (libsource (lib "Resistors") (part "Resistor - 0.1%"))
    )
    (comp (ref "R79")
      (value "10k")
      (footprint "RESC1005X35N")
      (description "Resistor - 0.1%")
      (fields
        (field (name "TOLERANCE") "±0.1%")
        (field (name "PART NUMBER") "R0402_10K_0.1%_0.063W_25PPM")
        (field (name "POWER") "0.063W")
        (field (name "AUTHOR") "CERN DEM JMW")
      )
      (libsource (lib "Resistors") (part "Resistor - 0.1%"))
    )
    (comp (ref "R80")
      (value "10k")
      (footprint "RESC1005X35N")
      (description "Resistor - 0.1%")
      (fields
        (field (name "TOLERANCE") "±0.1%")
        (field (name "PART NUMBER") "R0402_10K_0.1%_0.063W_25PPM")
        (field (name "POWER") "0.063W")
        (field (name "AUTHOR") "CERN DEM JMW")
      )
      (libsource (lib "Resistors") (part "Resistor - 0.1%"))
    )
    (comp (ref "R81")
      (value "10k")
      (footprint "RESC1005X35N")
      (description "Resistor - 0.1%")
      (fields
        (field (name "TOLERANCE") "±0.1%")
        (field (name "PART NUMBER") "R0402_10K_0.1%_0.063W_25PPM")
        (field (name "POWER") "0.063W")
        (field (name "AUTHOR") "CERN DEM JMW")
      )
      (libsource (lib "Resistors") (part "Resistor - 0.1%"))
    )
    (comp (ref "R82")
      (value "10k")
      (footprint "RESC1005X35N")
      (description "Resistor - 0.1%")
      (fields
        (field (name "TOLERANCE") "±0.1%")
        (field (name "PART NUMBER") "R0402_10K_0.1%_0.063W_25PPM")
        (field (name "POWER") "0.063W")
        (field (name "AUTHOR") "CERN DEM JMW")
      )
      (libsource (lib "Resistors") (part "Resistor - 0.1%"))
    )
    (comp (ref "R83")
      (value "10k")
      (footprint "RESC1005X35N")
      (description "Resistor - 0.1%")
      (fields
        (field (name "TOLERANCE") "±0.1%")
        (field (name "PART NUMBER") "R0402_10K_0.1%_0.063W_25PPM")
        (field (name "POWER") "0.063W")
        (field (name "AUTHOR") "CERN DEM JMW")
      )
      (libsource (lib "Resistors") (part "Resistor - 0.1%"))
    )
    (comp (ref "R84")
      (value "10k")
      (footprint "RESC1005X35N")
      (description "Resistor - 0.1%")
      (fields
        (field (name "TOLERANCE") "±0.1%")
        (field (name "PART NUMBER") "R0402_10K_0.1%_0.063W_25PPM")
        (field (name "POWER") "0.063W")
        (field (name "AUTHOR") "CERN DEM JMW")
      )
      (libsource (lib "Resistors") (part "Resistor - 0.1%"))
    )
    (comp (ref "R90")
      (value "220")
      (footprint "RESC1005X40N")
      (description "Resistor - 1%")
      (fields
        (field (name "TOLERANCE") "±1%")
        (field (name "PART NUMBER") "R0402_220R_1%_0.0625W_100PPM")
        (field (name "POWER") "0.0625W")
        (field (name "AUTHOR") "CERN DEM JLC")
      )
      (libsource (lib "Resistors") (part "Resistor - 1%"))
    )
    (comp (ref "R91")
      (value "10k")
      (footprint "RESC1005X35N")
      (description "Resistor - 0.1%")
      (fields
        (field (name "TOLERANCE") "±0.1%")
        (field (name "PART NUMBER") "R0402_10K_0.1%_0.063W_25PPM")
        (field (name "POWER") "0.063W")
        (field (name "AUTHOR") "CERN DEM JMW")
      )
      (libsource (lib "Resistors") (part "Resistor - 0.1%"))
    )
    (comp (ref "R92")
      (value "10k")
      (footprint "RESC1005X35N")
      (description "Resistor - 0.1%")
      (fields
        (field (name "TOLERANCE") "±0.1%")
        (field (name "PART NUMBER") "R0402_10K_0.1%_0.063W_25PPM")
        (field (name "POWER") "0.063W")
        (field (name "AUTHOR") "CERN DEM JMW")
      )
      (libsource (lib "Resistors") (part "Resistor - 0.1%"))
    )
    (comp (ref "SCREW1")
      (value "M2.5x4")
      (footprint "BOSSARD_BN5687-3061587_v")
      (description "Screw")
      (fields
        (field (name "PART NUMBER") "BOSSARD_BN5687-3061587_v")
        (field (name "MANUFACTURER") "BOSSARD")
        (field (name "AUTHOR") "CERN DEM JLC")
      )
      (libsource (lib "Eletro-mechanical") (part "Screw"))
    )
    (comp (ref "SCREW2")
      (value "M2.5x4")
      (footprint "BOSSARD_BN5687-3061587_v")
      (description "Screw")
      (fields
        (field (name "PART NUMBER") "BOSSARD_BN5687-3061587_v")
        (field (name "MANUFACTURER") "BOSSARD")
        (field (name "AUTHOR") "CERN DEM JLC")
      )
      (libsource (lib "Eletro-mechanical") (part "Screw"))
    )
    (comp (ref "SCREW3")
      (value "M2.5x4")
      (footprint "BOSSARD_BN5687-3061587_v")
      (description "Screw")
      (fields
        (field (name "PART NUMBER") "BOSSARD_BN5687-3061587_v")
        (field (name "MANUFACTURER") "BOSSARD")
        (field (name "AUTHOR") "CERN DEM JLC")
      )
      (libsource (lib "Eletro-mechanical") (part "Screw"))
    )
    (comp (ref "SCREW4")
      (value "M2.5x4")
      (footprint "BOSSARD_BN5687-3061587_v")
      (description "Screw")
      (fields
        (field (name "PART NUMBER") "BOSSARD_BN5687-3061587_v")
        (field (name "MANUFACTURER") "BOSSARD")
        (field (name "AUTHOR") "CERN DEM JLC")
      )
      (libsource (lib "Eletro-mechanical") (part "Screw"))
    )
    (comp (ref "SCREW5")
      (value "M2.5x4")
      (footprint "BOSSARD_BN5687-3061587_v")
      (description "Screw")
      (fields
        (field (name "PART NUMBER") "BOSSARD_BN5687-3061587_v")
        (field (name "MANUFACTURER") "BOSSARD")
        (field (name "AUTHOR") "CERN DEM JLC")
      )
      (libsource (lib "Eletro-mechanical") (part "Screw"))
    )
    (comp (ref "SCREW6")
      (value "M2.5x4")
      (footprint "BOSSARD_BN5687-3061587_v")
      (description "Screw")
      (fields
        (field (name "PART NUMBER") "BOSSARD_BN5687-3061587_v")
        (field (name "MANUFACTURER") "BOSSARD")
        (field (name "AUTHOR") "CERN DEM JLC")
      )
      (libsource (lib "Eletro-mechanical") (part "Screw"))
    )
    (comp (ref "T1")
      (value "BC857B")
      (footprint "SOT95P230X110-3N")
      (description "PNP Transistor")
      (fields (field (name "MANUFACTURER") "NXP SEMICONDUCTORS") (field (name "AUTHOR") "CERN DEM JLC"))
      (libsource (lib "ICs And Semiconductors") (part "PNP B1 E2 C3"))
    )
    (comp (ref "T2")
      (value "SQJ469EP-T1_BE3")
      (footprint "PowerPAK® SO-8L SINGLE")
      (libsource (lib "mb") (part "SQJ469EP-T1_BE3"))
    )
    (comp (ref "T3")
      (value "BC847C")
      (footprint "SOT95P240X110-3N")
      (description "NPN Transistor")
      (fields (field (name "MANUFACTURER") "INFINEON") (field (name "AUTHOR") "CERN DEM JLC"))
      (libsource (lib "ICs And Semiconductors") (part "NPN B1 E2 C3"))
    )
    (comp (ref "T4")
      (value "SQJ469EP-T1_BE3")
      (footprint "PowerPAK® SO-8L SINGLE")
      (libsource (lib "mb") (part "SQJ469EP-T1_BE3"))
    )
    (comp (ref "T5")
      (value "BSC600N25NS3GATMA1")
      (footprint "INFINEON_PG-TDSON-8")
      (description "MOSFET Transistor, N Channel, 25 A, 250 V, 0.05 ohm, 10 V, 3 V")
      (fields (field (name "MANUFACTURER") "Infineon"))
      (libsource (lib "mb") (part "BSC600N25NS3GATMA1"))
    )
    (comp (ref "T6")
      (value "BSS138LT1G")
      (footprint "SOT95P240X110-3N")
      (description "N-CHANNEL MOSFET WITH DIODE")
      (fields (field (name "AUTHOR") "CERN DEM JLC"))
      (libsource (lib "ICs And Semiconductors") (part "N-MOSFET-D 1G 2S 3D"))
    )
    (comp (ref "T7")
      (value "BSS138LT1G")
      (footprint "SOT95P240X110-3N")
      (description "N-CHANNEL MOSFET WITH DIODE")
      (fields (field (name "AUTHOR") "CERN DEM JLC"))
      (libsource (lib "ICs And Semiconductors") (part "N-MOSFET-D 1G 2S 3D"))
    )
  )
  (nets
    (net (code "1") (name "/BOOSTER_EN") (class "Default")
      (node (ref "IC1") (pin "5") (pinfunction "R_5") (pintype "output"))
      (node (ref "IC25") (pin "1") (pinfunction "A_1") (pintype "input"))
    )
    (net (code "2") (name "/BUCK_FB") (class "Default")
      (node (ref "T1") (pin "3") (pinfunction "C_3") (pintype "passive"))
    )
    (net (code "3") (name "/CABLE_DIR") (class "Default")
      (node (ref "IC22") (pin "4") (pinfunction "OUT_4") (pintype "output"))
      (node (ref "J1") (pin "17") (pinfunction "17_17") (pintype "bidirectional"))
      (node (ref "R81") (pin "1") (pinfunction "1_1") (pintype "passive"))
      (node (ref "R82") (pin "2") (pinfunction "2_2") (pintype "passive"))
    )
    (net (code "4") (name "/CABLE_ROLE") (class "Default")
      (node (ref "IC21") (pin "4") (pinfunction "OUT_4") (pintype "output"))
      (node (ref "J1") (pin "15") (pinfunction "15_15") (pintype "bidirectional"))
      (node (ref "R77") (pin "1") (pinfunction "1_1") (pintype "passive"))
      (node (ref "R78") (pin "2") (pinfunction "2_2") (pintype "passive"))
    )
    (net (code "5") (name "/COIL_DISCHARGE") (class "Default")
      (node (ref "IC24") (pin "4") (pinfunction "Y_4") (pintype "output"))
      (node (ref "IC7") (pin "3") (pinfunction "IN+/IN-_3") (pintype "input"))
    )
    (net (code "6") (name "/DP_KILL") (class "Default")
      (node (ref "IC2") (pin "5") (pinfunction "R_5") (pintype "output"))
      (node (ref "IC24") (pin "1") (pinfunction "A_1") (pintype "input"))
      (node (ref "IC26") (pin "2") (pinfunction "IN_2") (pintype "input"))
    )
    (net (code "7") (name "/EN_N") (class "Default")
      (node (ref "IC1") (pin "4") (pinfunction "B_4") (pintype "input"))
      (node (ref "J1") (pin "9") (pinfunction "9_9") (pintype "bidirectional"))
      (node (ref "R1") (pin "1") (pinfunction "1_1") (pintype "passive"))
    )
    (net (code "8") (name "/EN_P") (class "Default")
      (node (ref "IC1") (pin "3") (pinfunction "A_3") (pintype "input"))
      (node (ref "J1") (pin "7") (pinfunction "7_7") (pintype "bidirectional"))
      (node (ref "R1") (pin "2") (pinfunction "2_2") (pintype "passive"))
    )
    (net (code "9") (name "/EXT_IN") (class "Default")
      (node (ref "D6") (pin "1") (pinfunction "C_1") (pintype "passive"))
      (node (ref "J2") (pin "1") (pinfunction "Signal_1") (pintype "passive"))
      (node (ref "R90") (pin "2") (pinfunction "2_2") (pintype "passive"))
    )
    (net (code "10") (name "/EXT_KILL") (class "Default")
      (node (ref "IC19") (pin "4") (pinfunction "OUT_4") (pintype "open_collector"))
      (node (ref "IC24") (pin "2") (pinfunction "B_2") (pintype "input"))
    )
    (net (code "11") (name "/FAULT") (class "Default")
      (node (ref "IC9") (pin "4") (pinfunction "OUT_4") (pintype "open_collector"))
      (node (ref "J1") (pin "13") (pinfunction "13_13") (pintype "bidirectional"))
    )
    (net (code "12") (name "/IMON_N") (class "Default")
      (node (ref "J1") (pin "3") (pinfunction "3_3") (pintype "bidirectional"))
      (node (ref "R9") (pin "2") (pinfunction "2_2") (pintype "passive"))
    )
    (net (code "13") (name "/IMON_P") (class "Default")
      (node (ref "J1") (pin "1") (pinfunction "1_1") (pintype "bidirectional"))
      (node (ref "R27") (pin "2") (pinfunction "2_2") (pintype "passive"))
    )
    (net (code "14") (name "/ISET") (class "Default")
      (node (ref "IC3") (pin "3") (pinfunction "IN+_3") (pintype "input"))
      (node (ref "R24") (pin "2") (pinfunction "2_2") (pintype "passive"))
      (node (ref "R26") (pin "2") (pinfunction "2_2") (pintype "passive"))
    )
    (net (code "15") (name "/ISET_N") (class "Default")
      (node (ref "IC5") (pin "2") (pinfunction "IN-_2") (pintype "input"))
      (node (ref "J1") (pin "6") (pinfunction "6_6") (pintype "bidirectional"))
    )
    (net (code "16") (name "/ISET_P") (class "Default")
      (node (ref "IC5") (pin "3") (pinfunction "IN+_3") (pintype "input"))
      (node (ref "J1") (pin "4") (pinfunction "4_4") (pintype "bidirectional"))
    )
    (net (code "17") (name "/I_OUT_N") (class "Default")
      (node (ref "C7") (pin "1") (pinfunction "1_1") (pintype "passive"))
      (node (ref "D1") (pin "1") (pinfunction "C_1") (pintype "passive"))
      (node (ref "P2") (pin "1") (pinfunction "1_1") (pintype "passive"))
      (node (ref "T5") (pin "D") (pinfunction "D_D") (pintype "passive"))
    )
    (net (code "18") (name "/I_OUT_P") (class "Default")
      (node (ref "P2") (pin "2") (pinfunction "2_2") (pintype "passive"))
      (node (ref "R25") (pin "1") (pinfunction "1_1") (pintype "passive"))
      (node (ref "R28") (pin "2") (pinfunction "2_2") (pintype "passive"))
      (node (ref "T2") (pin "3") (pinfunction "D_3") (pintype "passive"))
      (node (ref "T4") (pin "3") (pinfunction "D_3") (pintype "passive"))
    )
    (net (code "19") (name "/KILL_N") (class "Default")
      (node (ref "IC2") (pin "4") (pinfunction "B_4") (pintype "input"))
      (node (ref "J1") (pin "12") (pinfunction "12_12") (pintype "bidirectional"))
      (node (ref "R3") (pin "1") (pinfunction "1_1") (pintype "passive"))
    )
    (net (code "20") (name "/KILL_P") (class "Default")
      (node (ref "IC2") (pin "3") (pinfunction "A_3") (pintype "input"))
      (node (ref "J1") (pin "10") (pinfunction "10_10") (pintype "bidirectional"))
      (node (ref "R3") (pin "2") (pinfunction "2_2") (pintype "passive"))
    )
    (net (code "21") (name "/OCP") (class "Default")
      (node (ref "IC10") (pin "1") (pinfunction "A_1") (pintype "input"))
      (node (ref "IC8") (pin "7") (pinfunction "OUT_7") (pintype "output"))
      (node (ref "R35") (pin "1") (pinfunction "1_1") (pintype "passive"))
      (node (ref "T6") (pin "1") (pinfunction "G_1") (pintype "passive"))
    )
    (net (code "22") (name "/OVERTEMP") (class "Default")
      (node (ref "IC10") (pin "2") (pinfunction "B_2") (pintype "input"))
      (node (ref "IC8") (pin "1") (pinfunction "OUT_1") (pintype "output"))
      (node (ref "R42") (pin "1") (pinfunction "1_1") (pintype "passive"))
      (node (ref "T7") (pin "1") (pinfunction "G_1") (pintype "passive"))
    )
    (net (code "23") (name "/POWER_IN") (class "Default")
      (node (ref "C12") (pin "1") (pinfunction "1_1") (pintype "passive"))
      (node (ref "D5") (pin "1") (pinfunction "C_1") (pintype "passive"))
      (node (ref "FL1") (pin "2") (pinfunction "CB_2") (pintype "passive"))
    )
    (net (code "24") (name "/SUPPLY_EN") (class "Default")
      (node (ref "IC25") (pin "4") (pinfunction "Y_4") (pintype "output"))
    )
    (net (code "25") (name "/VIN+") (class "Default")
      (node (ref "FL1") (pin "1") (pinfunction "B_1") (pintype "passive"))
      (node (ref "P1") (pin "1") (pinfunction "1_1") (pintype "passive"))
    )
    (net (code "26") (name "/VIN-") (class "Default")
      (node (ref "FL1") (pin "3") (pinfunction "PSG_3") (pintype "passive"))
      (node (ref "P1") (pin "2") (pinfunction "2_2") (pintype "passive"))
    )
    (net (code "27") (name "GND") (class "Default")
      (node (ref "B1") (pin "1") (pinfunction "1_1") (pintype "bidirectional"))
      (node (ref "B2") (pin "1") (pinfunction "1_1") (pintype "bidirectional"))
      (node (ref "C1") (pin "1") (pinfunction "1_1") (pintype "passive"))
      (node (ref "C10") (pin "1") (pinfunction "1_1") (pintype "passive"))
      (node (ref "C100") (pin "1") (pinfunction "1_1") (pintype "passive"))
      (node (ref "C101") (pin "1") (pinfunction "1_1") (pintype "passive"))
      (node (ref "C104") (pin "1") (pinfunction "1_1") (pintype "passive"))
      (node (ref "C11") (pin "1") (pinfunction "1_1") (pintype "passive"))
      (node (ref "C12") (pin "2") (pinfunction "2_2") (pintype "passive"))
      (node (ref "C13") (pin "1") (pinfunction "1_1") (pintype "passive"))
      (node (ref "C2") (pin "1") (pinfunction "1_1") (pintype "passive"))
      (node (ref "C3") (pin "1") (pinfunction "1_1") (pintype "passive"))
      (node (ref "C4") (pin "1") (pinfunction "1_1") (pintype "passive"))
      (node (ref "C40") (pin "1") (pinfunction "1_1") (pintype "passive"))
      (node (ref "C48") (pin "1") (pinfunction "1_1") (pintype "passive"))
      (node (ref "C5") (pin "1") (pinfunction "1_1") (pintype "passive"))
      (node (ref "C56") (pin "1") (pinfunction "1_1") (pintype "passive"))
      (node (ref "C8") (pin "1") (pinfunction "1_1") (pintype "passive"))
      (node (ref "C9") (pin "1") (pinfunction "1_1") (pintype "passive"))
      (node (ref "C94") (pin "1") (pinfunction "1_1") (pintype "passive"))
      (node (ref "C95") (pin "1") (pinfunction "1_1") (pintype "passive"))
      (node (ref "C96") (pin "1") (pinfunction "1_1") (pintype "passive"))
      (node (ref "C97") (pin "1") (pinfunction "1_1") (pintype "passive"))
      (node (ref "C98") (pin "1") (pinfunction "1_1") (pintype "passive"))
      (node (ref "C99") (pin "1") (pinfunction "1_1") (pintype "passive"))
      (node (ref "D1") (pin "2") (pinfunction "A_2") (pintype "passive"))
      (node (ref "D5") (pin "2") (pinfunction "A_2") (pintype "passive"))
      (node (ref "D6") (pin "2") (pinfunction "A_2") (pintype "passive"))
      (node (ref "FL1") (pin "4") (pinfunction "CG_4") (pintype "passive"))
      (node (ref "IC1") (pin "2") (pinfunction "GND_2") (pintype "power_in"))
      (node (ref "IC10") (pin "3") (pinfunction "GND_3") (pintype "power_in"))
      (node (ref "IC11") (pin "3") (pinfunction "GND_3") (pintype "power_in"))
      (node (ref "IC19") (pin "3") (pinfunction "GND_3") (pintype "power_in"))
      (node (ref "IC2") (pin "2") (pinfunction "GND_2") (pintype "power_in"))
      (node (ref "IC21") (pin "2") (pinfunction "V-_2") (pintype "power_in"))
      (node (ref "IC22") (pin "2") (pinfunction "V-_2") (pintype "power_in"))
      (node (ref "IC24") (pin "3") (pinfunction "GND_3") (pintype "power_in"))
      (node (ref "IC25") (pin "3") (pinfunction "GND_3") (pintype "power_in"))
      (node (ref "IC26") (pin "3") (pinfunction "GND_3") (pintype "power_in"))
      (node (ref "IC3") (pin "4") (pinfunction "V-_4") (pintype "power_in"))
      (node (ref "IC4") (pin "5") (pinfunction "REF_5") (pintype "input"))
      (node (ref "IC7") (pin "2") (pinfunction "GND_2") (pintype "power_in"))
      (node (ref "IC8") (pin "4") (pinfunction "V-_4") (pintype "power_in"))
      (node (ref "IC9") (pin "3") (pinfunction "GND_3") (pintype "power_in"))
      (node (ref "J1") (pin "11") (pinfunction "11_11") (pintype "bidirectional"))
      (node (ref "J1") (pin "16") (pinfunction "16_16") (pintype "bidirectional"))
      (node (ref "J1") (pin "19") (pinfunction "19_19") (pintype "bidirectional"))
      (node (ref "J1") (pin "2") (pinfunction "2_2") (pintype "bidirectional"))
      (node (ref "J1") (pin "5") (pinfunction "5_5") (pintype "bidirectional"))
      (node (ref "J1") (pin "8") (pinfunction "8_8") (pintype "bidirectional"))
      (node (ref "J1") (pin "SHIELD") (pinfunction "SHIELD_SHIELD") (pintype "power_in"))
      (node (ref "J2") (pin "2") (pinfunction "GND_2") (pintype "passive"))
      (node (ref "J2") (pin "3") (pinfunction "GND_3") (pintype "passive"))
      (node (ref "J2") (pin "4") (pinfunction "GND_4") (pintype "passive"))
      (node (ref "J2") (pin "5") (pinfunction "GND_5") (pintype "passive"))
      (node (ref "R26") (pin "1") (pinfunction "1_1") (pintype "passive"))
      (node (ref "R30") (pin "1") (pinfunction "1_1") (pintype "passive"))
      (node (ref "R37") (pin "1") (pinfunction "1_1") (pintype "passive"))
      (node (ref "R38") (pin "1") (pinfunction "1_1") (pintype "passive"))
      (node (ref "R39") (pin "1") (pinfunction "1_1") (pintype "passive"))
      (node (ref "R41") (pin "1") (pinfunction "1_1") (pintype "passive"))
      (node (ref "R80") (pin "1") (pinfunction "1_1") (pintype "passive"))
      (node (ref "R84") (pin "1") (pinfunction "1_1") (pintype "passive"))
      (node (ref "T5") (pin "1") (pinfunction "S_1") (pintype "passive"))
      (node (ref "T5") (pin "2") (pinfunction "S_2") (pintype "passive"))
      (node (ref "T5") (pin "3") (pinfunction "S_3") (pintype "passive"))
      (node (ref "T6") (pin "2") (pinfunction "S_2") (pintype "passive"))
      (node (ref "T7") (pin "2") (pinfunction "S_2") (pintype "passive"))
    )
    (net (code "28") (name "N15V0") (class "Default")
      (node (ref "C3") (pin "2") (pinfunction "2_2") (pintype "passive"))
      (node (ref "C95") (pin "2") (pinfunction "2_2") (pintype "passive"))
      (node (ref "C97") (pin "2") (pinfunction "2_2") (pintype "passive"))
      (node (ref "IC4") (pin "4") (pinfunction "-Vs_4") (pintype "power_in"))
      (node (ref "IC5") (pin "4") (pinfunction "-VEE_4") (pintype "power_in"))
      (node (ref "IC6") (pin "4") (pinfunction "V-_4") (pintype "power_in"))
    )
    (net (code "29") (name "Net-(C7-Pad2)") (class "Default")
      (node (ref "C7") (pin "2") (pinfunction "2_2") (pintype "passive"))
      (node (ref "R28") (pin "1") (pinfunction "1_1") (pintype "passive"))
    )
    (net (code "30") (name "Net-(C13-Pad2)") (class "Default")
      (node (ref "C13") (pin "2") (pinfunction "2_2") (pintype "passive"))
      (node (ref "R43") (pin "1") (pinfunction "1_1") (pintype "passive"))
    )
    (net (code "31") (name "Net-(C103-Pad2)") (class "Default")
      (node (ref "C103") (pin "2") (pinfunction "2_2") (pintype "passive"))
      (node (ref "R15") (pin "2") (pinfunction "2_2") (pintype "passive"))
    )
    (net (code "32") (name "Net-(IC3A-IN-)") (class "Default")
      (node (ref "IC3") (pin "2") (pinfunction "IN-_2") (pintype "input"))
      (node (ref "R30") (pin "2") (pinfunction "2_2") (pintype "passive"))
      (node (ref "T3") (pin "2") (pinfunction "E_2") (pintype "passive"))
    )
    (net (code "33") (name "Net-(IC3A-OUT)") (class "Default")
      (node (ref "IC3") (pin "1") (pinfunction "OUT_1") (pintype "output"))
      (node (ref "T3") (pin "1") (pinfunction "B_1") (pintype "passive"))
    )
    (net (code "34") (name "Net-(IC3B-IN+)") (class "Default")
      (node (ref "IC3") (pin "5") (pinfunction "IN+_5") (pintype "input"))
      (node (ref "R18") (pin "1") (pinfunction "1_1") (pintype "passive"))
      (node (ref "R19") (pin "1") (pinfunction "1_1") (pintype "passive"))
      (node (ref "T3") (pin "3") (pinfunction "C_3") (pintype "passive"))
    )
    (net (code "35") (name "Net-(IC3B-IN-)") (class "Default")
      (node (ref "C6") (pin "2") (pinfunction "2_2") (pintype "passive"))
      (node (ref "IC3") (pin "6") (pinfunction "IN-_6") (pintype "input"))
      (node (ref "R12") (pin "1") (pinfunction "1_1") (pintype "passive"))
    )
    (net (code "36") (name "Net-(IC3B-OUT)") (class "Default")
      (node (ref "C6") (pin "1") (pinfunction "1_1") (pintype "passive"))
      (node (ref "IC3") (pin "7") (pinfunction "OUT_7") (pintype "output"))
      (node (ref "R20") (pin "1") (pinfunction "1_1") (pintype "passive"))
      (node (ref "R22") (pin "1") (pinfunction "1_1") (pintype "passive"))
    )
    (net (code "37") (name "Net-(IC4-+IN)") (class "Default")
      (node (ref "IC4") (pin "3") (pinfunction "+IN_3") (pintype "input"))
      (node (ref "R10") (pin "2") (pinfunction "2_2") (pintype "passive"))
    )
    (net (code "38") (name "Net-(IC4-+RG)") (class "Default")
      (node (ref "IC4") (pin "8") (pinfunction "+RG_8") (pintype "passive"))
      (node (ref "R8") (pin "2") (pinfunction "2_2") (pintype "passive"))
    )
    (net (code "39") (name "Net-(IC4--IN)") (class "Default")
      (node (ref "IC4") (pin "2") (pinfunction "-IN_2") (pintype "input"))
      (node (ref "R4") (pin "2") (pinfunction "2_2") (pintype "passive"))
    )
    (net (code "40") (name "Net-(IC4--RG)") (class "Default")
      (node (ref "IC4") (pin "1") (pinfunction "-RG_1") (pintype "passive"))
      (node (ref "R6") (pin "2") (pinfunction "2_2") (pintype "passive"))
    )
    (net (code "41") (name "Net-(IC4-Vout)") (class "Default")
      (node (ref "IC4") (pin "6") (pinfunction "Vout_6") (pintype "output"))
      (node (ref "R13") (pin "2") (pinfunction "2_2") (pintype "passive"))
      (node (ref "R7") (pin "1") (pinfunction "1_1") (pintype "passive"))
    )
    (net (code "42") (name "Net-(IC5-OUT)") (class "Default")
      (node (ref "IC5") (pin "5") (pinfunction "SENS_5") (pintype "passive"))
      (node (ref "IC5") (pin "6") (pinfunction "OUT_6") (pintype "output"))
      (node (ref "R23") (pin "1") (pinfunction "1_1") (pintype "passive"))
    )
    (net (code "43") (name "Net-(IC6A-IN+)") (class "Default")
      (node (ref "IC6") (pin "3") (pinfunction "IN+_3") (pintype "input"))
      (node (ref "R11") (pin "2") (pinfunction "2_2") (pintype "passive"))
      (node (ref "R14") (pin "2") (pinfunction "2_2") (pintype "passive"))
    )
    (net (code "44") (name "Net-(IC6A-IN-)") (class "Default")
      (node (ref "IC6") (pin "2") (pinfunction "IN-_2") (pintype "input"))
      (node (ref "R2") (pin "2") (pinfunction "2_2") (pintype "passive"))
      (node (ref "R7") (pin "2") (pinfunction "2_2") (pintype "passive"))
    )
    (net (code "45") (name "Net-(IC6A-OUT)") (class "Default")
      (node (ref "IC6") (pin "1") (pinfunction "OUT_1") (pintype "output"))
      (node (ref "R16") (pin "2") (pinfunction "2_2") (pintype "passive"))
      (node (ref "R2") (pin "1") (pinfunction "1_1") (pintype "passive"))
      (node (ref "R9") (pin "1") (pinfunction "1_1") (pintype "passive"))
    )
    (net (code "46") (name "Net-(IC6B-IN+)") (class "Default")
      (node (ref "IC6") (pin "5") (pinfunction "IN+_5") (pintype "input"))
      (node (ref "R29") (pin "2") (pinfunction "2_2") (pintype "passive"))
      (node (ref "R31") (pin "2") (pinfunction "2_2") (pintype "passive"))
    )
    (net (code "47") (name "Net-(IC6B-IN-)") (class "Default")
      (node (ref "IC6") (pin "6") (pinfunction "IN-_6") (pintype "input"))
      (node (ref "R16") (pin "1") (pinfunction "1_1") (pintype "passive"))
      (node (ref "R21") (pin "2") (pinfunction "2_2") (pintype "passive"))
    )
    (net (code "48") (name "Net-(IC6B-OUT)") (class "Default")
      (node (ref "IC6") (pin "7") (pinfunction "OUT_7") (pintype "output"))
      (node (ref "R21") (pin "1") (pinfunction "1_1") (pintype "passive"))
      (node (ref "R27") (pin "1") (pinfunction "1_1") (pintype "passive"))
    )
    (net (code "49") (name "Net-(IC7-OUT)") (class "Default")
      (node (ref "IC7") (pin "4") (pinfunction "OUT_4") (pintype "output"))
      (node (ref "R36") (pin "1") (pinfunction "1_1") (pintype "passive"))
    )
    (net (code "50") (name "Net-(IC8A-IN-)") (class "Default")
      (node (ref "IC8") (pin "2") (pinfunction "IN-_2") (pintype "input"))
      (node (ref "R40") (pin "1") (pinfunction "1_1") (pintype "passive"))
      (node (ref "R41") (pin "2") (pinfunction "2_2") (pintype "passive"))
    )
    (net (code "51") (name "Net-(IC8B-IN+)") (class "Default")
      (node (ref "IC8") (pin "5") (pinfunction "IN+_5") (pintype "input"))
      (node (ref "R13") (pin "1") (pinfunction "1_1") (pintype "passive"))
      (node (ref "R38") (pin "2") (pinfunction "2_2") (pintype "passive"))
      (node (ref "R39") (pin "2") (pinfunction "2_2") (pintype "passive"))
    )
    (net (code "52") (name "Net-(IC8B-IN-)") (class "Default")
      (node (ref "IC8") (pin "6") (pinfunction "IN-_6") (pintype "input"))
      (node (ref "R32") (pin "1") (pinfunction "1_1") (pintype "passive"))
      (node (ref "R33") (pin "2") (pinfunction "2_2") (pintype "passive"))
    )
    (net (code "53") (name "Net-(IC10-Y)") (class "Default")
      (node (ref "IC10") (pin "4") (pinfunction "Y_4") (pintype "output"))
      (node (ref "IC9") (pin "2") (pinfunction "IN_2") (pintype "input"))
    )
    (net (code "54") (name "Net-(IC11-Vo)") (class "Default")
      (node (ref "IC11") (pin "2") (pinfunction "Vo_2") (pintype "output"))
      (node (ref "IC8") (pin "3") (pinfunction "IN+_3") (pintype "input"))
      (node (ref "R43") (pin "2") (pinfunction "2_2") (pintype "passive"))
    )
    (net (code "55") (name "Net-(IC19-IN)") (class "Default")
      (node (ref "IC19") (pin "2") (pinfunction "IN_2") (pintype "input"))
      (node (ref "R90") (pin "1") (pinfunction "1_1") (pintype "passive"))
    )
    (net (code "56") (name "Net-(IC21-IN+)") (class "Default")
      (node (ref "IC21") (pin "1") (pinfunction "IN+_1") (pintype "input"))
      (node (ref "R79") (pin "1") (pinfunction "1_1") (pintype "passive"))
      (node (ref "R80") (pin "2") (pinfunction "2_2") (pintype "passive"))
    )
    (net (code "57") (name "Net-(IC21-IN-)") (class "Default")
      (node (ref "IC21") (pin "3") (pinfunction "IN-_3") (pintype "input"))
      (node (ref "R78") (pin "1") (pinfunction "1_1") (pintype "passive"))
      (node (ref "R91") (pin "2") (pinfunction "2_2") (pintype "passive"))
    )
    (net (code "58") (name "Net-(IC22-IN+)") (class "Default")
      (node (ref "IC22") (pin "1") (pinfunction "IN+_1") (pintype "input"))
      (node (ref "R83") (pin "1") (pinfunction "1_1") (pintype "passive"))
      (node (ref "R84") (pin "2") (pinfunction "2_2") (pintype "passive"))
    )
    (net (code "59") (name "Net-(IC22-IN-)") (class "Default")
      (node (ref "IC22") (pin "3") (pinfunction "IN-_3") (pintype "input"))
      (node (ref "R81") (pin "2") (pinfunction "2_2") (pintype "passive"))
      (node (ref "R82") (pin "1") (pinfunction "1_1") (pintype "passive"))
    )
    (net (code "60") (name "Net-(IC25-B)") (class "Default")
      (node (ref "IC25") (pin "2") (pinfunction "B_2") (pintype "input"))
      (node (ref "IC26") (pin "4") (pinfunction "OUT_4") (pintype "output"))
    )
    (net (code "61") (name "Net-(LD1-C)") (class "Default")
      (node (ref "LD1") (pin "1") (pinfunction "C_1") (pintype "passive"))
      (node (ref "R44") (pin "2") (pinfunction "2_2") (pintype "passive"))
    )
    (net (code "62") (name "Net-(LD2-C)") (class "Default")
      (node (ref "LD2") (pin "1") (pinfunction "C_1") (pintype "passive"))
      (node (ref "R45") (pin "2") (pinfunction "2_2") (pintype "passive"))
    )
    (net (code "63") (name "Net-(R4-Pad1)") (class "Default")
      (node (ref "R4") (pin "1") (pinfunction "1_1") (pintype "passive"))
      (node (ref "R5") (pin "V2") (pinfunction "V2_V2") (pintype "passive"))
    )
    (net (code "64") (name "Net-(R6-Pad1)") (class "Default")
      (node (ref "R6") (pin "1") (pinfunction "1_1") (pintype "passive"))
      (node (ref "R8") (pin "1") (pinfunction "1_1") (pintype "passive"))
    )
    (net (code "65") (name "Net-(R10-Pad1)") (class "Default")
      (node (ref "R10") (pin "1") (pinfunction "1_1") (pintype "passive"))
      (node (ref "R5") (pin "V1") (pinfunction "V1_V1") (pintype "passive"))
    )
    (net (code "66") (name "Net-(R23-Pad2)") (class "Default")
      (node (ref "R23") (pin "2") (pinfunction "2_2") (pintype "passive"))
      (node (ref "R24") (pin "1") (pinfunction "1_1") (pintype "passive"))
    )
    (net (code "67") (name "Net-(R33-Pad1)") (class "Default")
      (node (ref "R33") (pin "1") (pinfunction "1_1") (pintype "passive"))
      (node (ref "R34") (pin "2") (pinfunction "2_2") (pintype "passive"))
    )
    (net (code "68") (name "Net-(R34-Pad1)") (class "Default")
      (node (ref "R34") (pin "1") (pinfunction "1_1") (pintype "passive"))
      (node (ref "R37") (pin "2") (pinfunction "2_2") (pintype "passive"))
    )
    (net (code "69") (name "Net-(R77-Pad2)") (class "Default")
      (node (ref "R77") (pin "2") (pinfunction "2_2") (pintype "passive"))
      (node (ref "R91") (pin "1") (pinfunction "1_1") (pintype "passive"))
    )
    (net (code "70") (name "Net-(R79-Pad2)") (class "Default")
      (node (ref "R79") (pin "2") (pinfunction "2_2") (pintype "passive"))
      (node (ref "R92") (pin "1") (pinfunction "1_1") (pintype "passive"))
    )
    (net (code "71") (name "Net-(T1-B)") (class "Default")
      (node (ref "R25") (pin "2") (pinfunction "2_2") (pintype "passive"))
      (node (ref "T1") (pin "1") (pinfunction "B_1") (pintype "passive"))
    )
    (net (code "72") (name "Net-(T1-E)") (class "Default")
      (node (ref "C103") (pin "1") (pinfunction "1_1") (pintype "passive"))
      (node (ref "R17") (pin "2") (pinfunction "2_2") (pintype "passive"))
      (node (ref "T1") (pin "2") (pinfunction "E_2") (pintype "passive"))
    )
    (net (code "73") (name "Net-(T2-G)") (class "Default")
      (node (ref "R20") (pin "2") (pinfunction "2_2") (pintype "passive"))
      (node (ref "T2") (pin "1") (pinfunction "G_1") (pintype "passive"))
    )
    (net (code "74") (name "Net-(T2-S)") (class "Default")
      (node (ref "R12") (pin "2") (pinfunction "2_2") (pintype "passive"))
      (node (ref "R15") (pin "1") (pinfunction "1_1") (pintype "passive"))
      (node (ref "R17") (pin "1") (pinfunction "1_1") (pintype "passive"))
      (node (ref "R5") (pin "I2") (pinfunction "I2_I2") (pintype "passive"))
      (node (ref "T2") (pin "2") (pinfunction "S_2") (pintype "passive"))
      (node (ref "T4") (pin "2") (pinfunction "S_2") (pintype "passive"))
    )
    (net (code "75") (name "Net-(T4-G)") (class "Default")
      (node (ref "R22") (pin "2") (pinfunction "2_2") (pintype "passive"))
      (node (ref "T4") (pin "1") (pinfunction "G_1") (pintype "passive"))
    )
    (net (code "76") (name "Net-(T5-G)") (class "Default")
      (node (ref "R36") (pin "2") (pinfunction "2_2") (pintype "passive"))
      (node (ref "T5") (pin "4") (pinfunction "G_4") (pintype "passive"))
    )
    (net (code "77") (name "Net-(T6-D)") (class "Default")
      (node (ref "R44") (pin "1") (pinfunction "1_1") (pintype "passive"))
      (node (ref "T6") (pin "3") (pinfunction "D_3") (pintype "passive"))
    )
    (net (code "78") (name "Net-(T7-D)") (class "Default")
      (node (ref "R45") (pin "1") (pinfunction "1_1") (pintype "passive"))
      (node (ref "T7") (pin "3") (pinfunction "D_3") (pintype "passive"))
    )
    (net (code "79") (name "P2V5_REF") (class "Default")
      (node (ref "IC5") (pin "1") (pinfunction "REF_1") (pintype "passive"))
      (node (ref "R11") (pin "1") (pinfunction "1_1") (pintype "passive"))
      (node (ref "R14") (pin "1") (pinfunction "1_1") (pintype "passive"))
      (node (ref "R29") (pin "1") (pinfunction "1_1") (pintype "passive"))
      (node (ref "R31") (pin "1") (pinfunction "1_1") (pintype "passive"))
      (node (ref "R83") (pin "2") (pinfunction "2_2") (pintype "passive"))
      (node (ref "R92") (pin "2") (pinfunction "2_2") (pintype "passive"))
    )
    (net (code "80") (name "P3V3") (class "Default")
      (node (ref "C1") (pin "2") (pinfunction "2_2") (pintype "passive"))
      (node (ref "C100") (pin "2") (pinfunction "2_2") (pintype "passive"))
      (node (ref "C101") (pin "2") (pinfunction "2_2") (pintype "passive"))
      (node (ref "C104") (pin "2") (pinfunction "2_2") (pintype "passive"))
      (node (ref "C4") (pin "2") (pinfunction "2_2") (pintype "passive"))
      (node (ref "C40") (pin "2") (pinfunction "2_2") (pintype "passive"))
      (node (ref "C48") (pin "2") (pinfunction "2_2") (pintype "passive"))
      (node (ref "C56") (pin "2") (pinfunction "2_2") (pintype "passive"))
      (node (ref "C9") (pin "2") (pinfunction "2_2") (pintype "passive"))
      (node (ref "C98") (pin "2") (pinfunction "2_2") (pintype "passive"))
      (node (ref "C99") (pin "2") (pinfunction "2_2") (pintype "passive"))
      (node (ref "IC1") (pin "1") (pinfunction "VCC_1") (pintype "power_in"))
      (node (ref "IC10") (pin "5") (pinfunction "VCC_5") (pintype "power_in"))
      (node (ref "IC19") (pin "5") (pinfunction "VCC_5") (pintype "power_in"))
      (node (ref "IC2") (pin "1") (pinfunction "VCC_1") (pintype "power_in"))
      (node (ref "IC21") (pin "5") (pinfunction "V+_5") (pintype "power_in"))
      (node (ref "IC22") (pin "5") (pinfunction "V+_5") (pintype "power_in"))
      (node (ref "IC24") (pin "5") (pinfunction "VCC_5") (pintype "power_in"))
      (node (ref "IC25") (pin "5") (pinfunction "VCC_5") (pintype "power_in"))
      (node (ref "IC26") (pin "5") (pinfunction "VCC_5") (pintype "power_in"))
      (node (ref "IC8") (pin "8") (pinfunction "V+_8") (pintype "power_in"))
      (node (ref "IC9") (pin "5") (pinfunction "VCC_5") (pintype "power_in"))
      (node (ref "LD1") (pin "2") (pinfunction "A_2") (pintype "passive"))
      (node (ref "LD2") (pin "2") (pinfunction "A_2") (pintype "passive"))
      (node (ref "R32") (pin "2") (pinfunction "2_2") (pintype "passive"))
      (node (ref "R35") (pin "2") (pinfunction "2_2") (pintype "passive"))
      (node (ref "R40") (pin "2") (pinfunction "2_2") (pintype "passive"))
      (node (ref "R42") (pin "2") (pinfunction "2_2") (pintype "passive"))
    )
    (net (code "81") (name "P5V4A") (class "Default")
      (node (ref "C10") (pin "2") (pinfunction "2_2") (pintype "passive"))
      (node (ref "C11") (pin "2") (pinfunction "2_2") (pintype "passive"))
      (node (ref "IC11") (pin "1") (pinfunction "+Vs_1") (pintype "power_in"))
    )
    (net (code "82") (name "P12V0") (class "Default")
      (node (ref "C8") (pin "2") (pinfunction "2_2") (pintype "passive"))
      (node (ref "IC7") (pin "1") (pinfunction "ENA_1") (pintype "input"))
      (node (ref "IC7") (pin "5") (pinfunction "VDD_5") (pintype "power_in"))
    )
    (net (code "83") (name "P15V0") (class "Default")
      (node (ref "C2") (pin "2") (pinfunction "2_2") (pintype "passive"))
      (node (ref "C5") (pin "2") (pinfunction "2_2") (pintype "passive"))
      (node (ref "C94") (pin "2") (pinfunction "2_2") (pintype "passive"))
      (node (ref "C96") (pin "2") (pinfunction "2_2") (pintype "passive"))
      (node (ref "IC3") (pin "8") (pinfunction "V+_8") (pintype "power_in"))
      (node (ref "IC4") (pin "7") (pinfunction "+Vs_7") (pintype "power_in"))
      (node (ref "IC5") (pin "7") (pinfunction "+VCC_7") (pintype "power_in"))
      (node (ref "IC6") (pin "8") (pinfunction "V+_8") (pintype "power_in"))
    )
    (net (code "84") (name "VBUCK") (class "Default")
      (node (ref "R18") (pin "2") (pinfunction "2_2") (pintype "passive"))
      (node (ref "R19") (pin "2") (pinfunction "2_2") (pintype "passive"))
      (node (ref "R5") (pin "I1") (pinfunction "I1_I1") (pintype "passive"))
    )
    (net (code "85") (name "unconnected-(B3-Pad1)") (class "Default")
      (node (ref "B3") (pin "1") (pinfunction "1_1") (pintype "bidirectional"))
    )
    (net (code "86") (name "unconnected-(B4-Pad1)") (class "Default")
      (node (ref "B4") (pin "1") (pinfunction "1_1") (pintype "bidirectional"))
    )
    (net (code "87") (name "unconnected-(B5-Pad1)") (class "Default")
      (node (ref "B5") (pin "1") (pinfunction "1_1") (pintype "bidirectional"))
    )
    (net (code "88") (name "unconnected-(B6-Pad1)") (class "Default")
      (node (ref "B6") (pin "1") (pinfunction "1_1") (pintype "bidirectional"))
    )
    (net (code "89") (name "unconnected-(B7-Pad1)") (class "Default")
      (node (ref "B7") (pin "1") (pinfunction "1_1") (pintype "bidirectional"))
    )
    (net (code "90") (name "unconnected-(B8-Pad1)") (class "Default")
      (node (ref "B8") (pin "1") (pinfunction "1_1") (pintype "bidirectional"))
    )
    (net (code "91") (name "unconnected-(J1-Pad14)") (class "Default")
      (node (ref "J1") (pin "14") (pinfunction "14_14") (pintype "bidirectional"))
    )
    (net (code "92") (name "unconnected-(J1-Pad18)") (class "Default")
      (node (ref "J1") (pin "18") (pinfunction "18_18") (pintype "bidirectional"))
    )
    (net (code "93") (name "unconnected-(J1-Pad20)") (class "Default")
      (node (ref "J1") (pin "20") (pinfunction "20_20") (pintype "bidirectional"))
    )
  )
)
